# NEOPUUTA.net
KiCad netlist of a schematic drawn in EAGLE
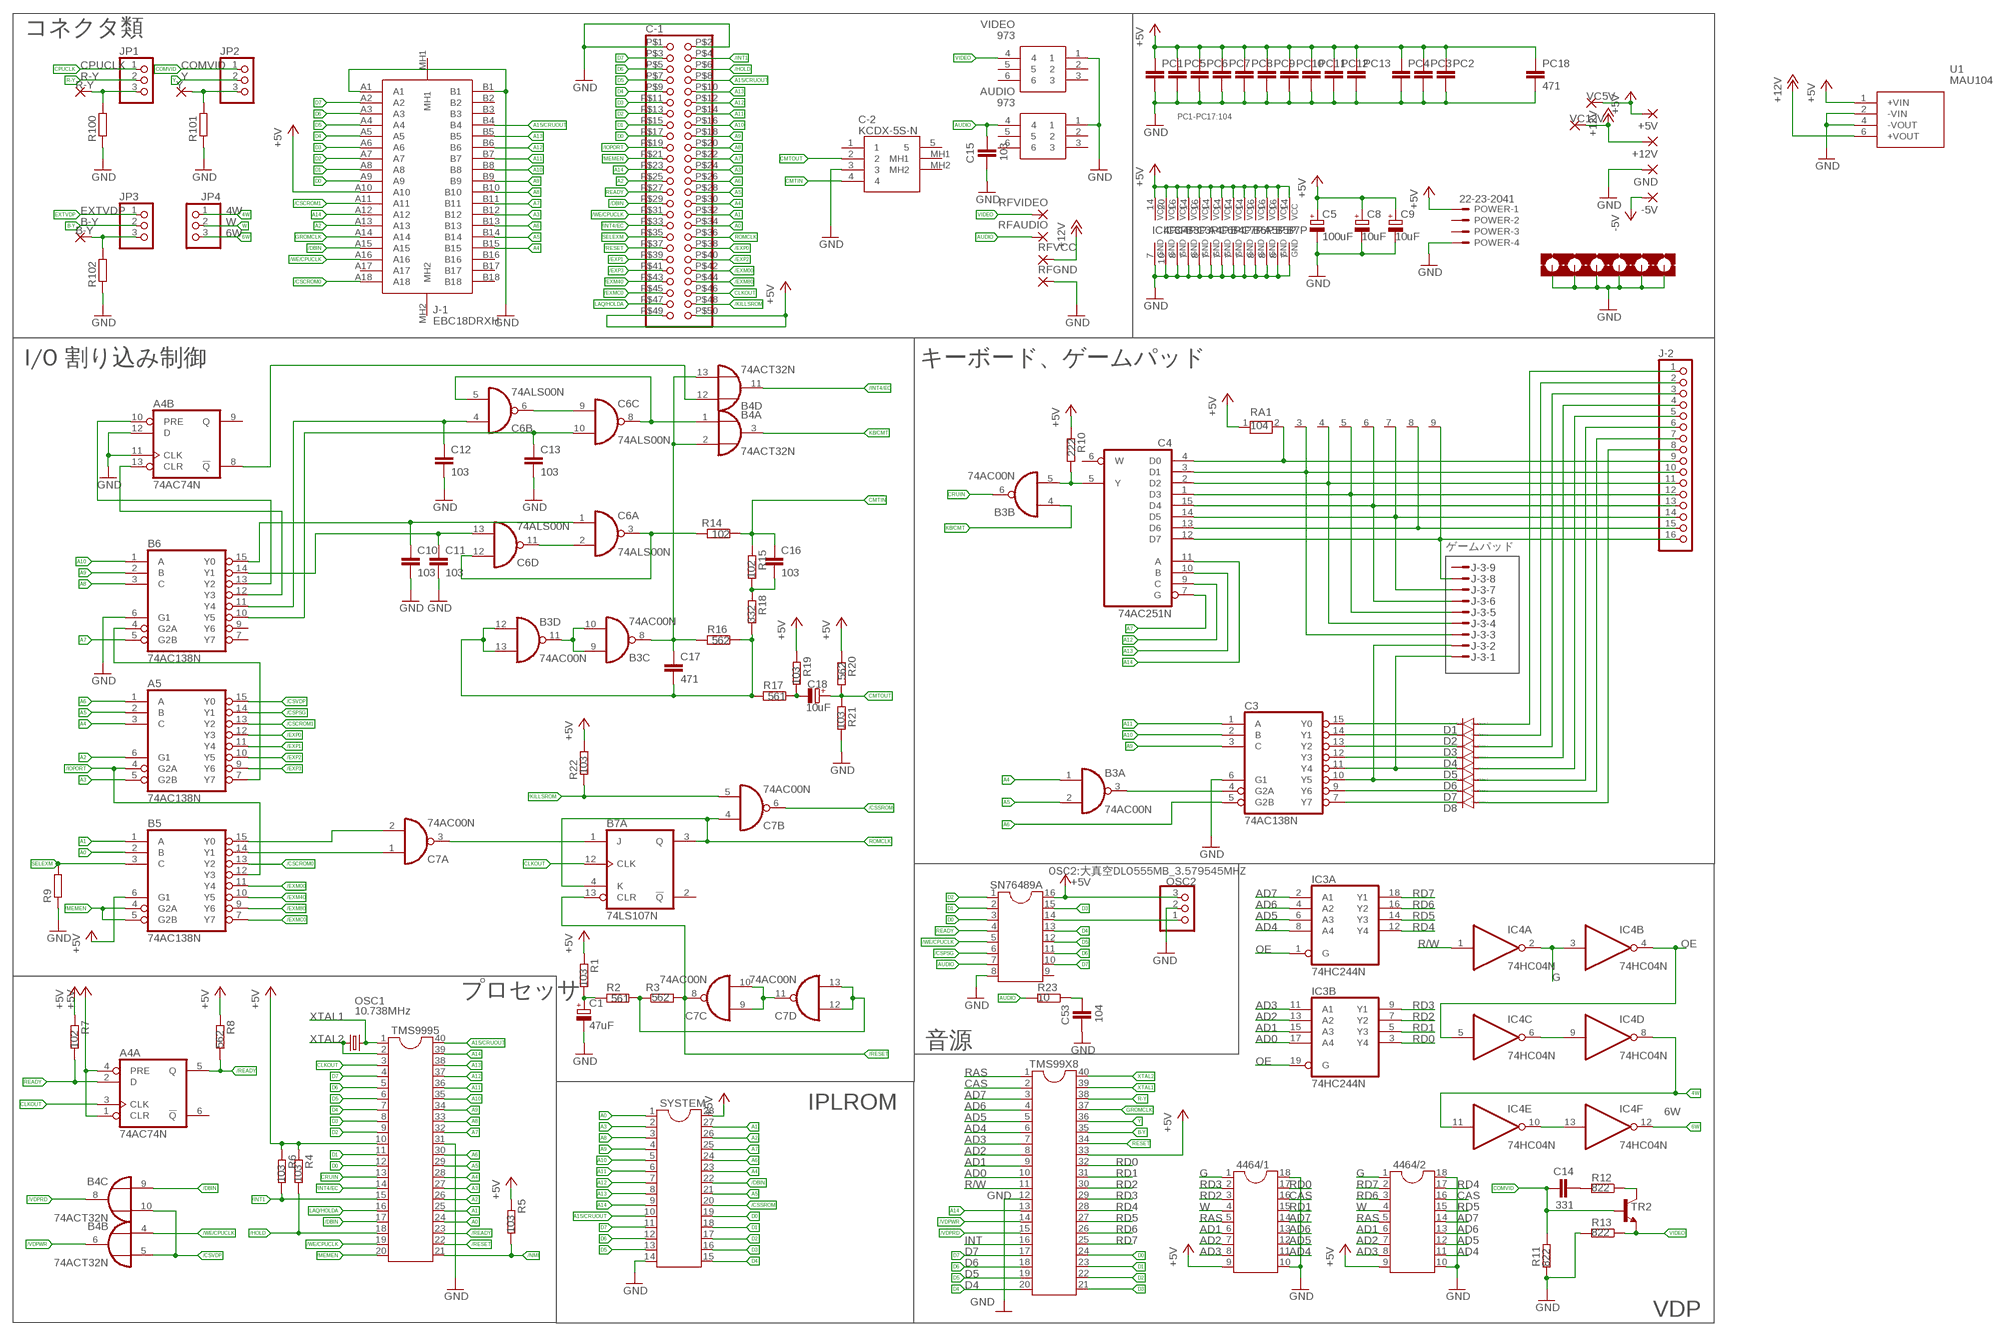
[diagram p0: schematic, sheet 1]

(export (version "E")
  (design (tool "Eeschema 10.0.6"))
  (components
    (comp (ref "+5V")
      (value "3,81/1,4")
      (footprint "eagle-import:3,81_1,4")
      (libsource (lib "eagle-import") (part "3,81/1,4"))
    )
    (comp (ref "+12V")
      (value "3,81/1,4")
      (footprint "eagle-import:3,81_1,4")
      (libsource (lib "eagle-import") (part "3,81/1,4"))
    )
    (comp (ref "-5V")
      (value "3,81/1,4")
      (footprint "eagle-import:3,81_1,4")
      (libsource (lib "eagle-import") (part "3,81/1,4"))
    )
    (comp (ref "4464/1")
      (value "DIL18")
      (footprint "eagle-import:DIL18")
      (libsource (lib "eagle-import") (part "DIL18"))
    )
    (comp (ref "4464/2")
      (value "DIL18")
      (footprint "eagle-import:DIL18")
      (libsource (lib "eagle-import") (part "DIL18"))
    )
    (comp (ref "A4")
      (value "74AC74N")
      (footprint "eagle-import:DIL14")
      (libsource (lib "eagle-import") (part "7474NAC"))
    )
    (comp (ref "A5")
      (value "74AC138N")
      (footprint "eagle-import:DIL16")
      (libsource (lib "eagle-import") (part "74138NAC"))
    )
    (comp (ref "AUDIO")
      (value "973")
      (footprint "eagle-import:973_1")
      (fields (field (name "MOUSER_PART_NUMBER") "534-973"))
      (libsource (lib "eagle-import") (part "973"))
    )
    (comp (ref "B-Y")
      (value "1,6/0,9")
      (footprint "eagle-import:1,6_0,9")
      (libsource (lib "eagle-import") (part "1,6/0,9"))
    )
    (comp (ref "B3")
      (value "74AC00N")
      (footprint "eagle-import:DIL14")
      (libsource (lib "eagle-import") (part "7400NAC"))
    )
    (comp (ref "B4")
      (value "74ACT32N")
      (footprint "eagle-import:DIL14")
      (libsource (lib "eagle-import") (part "7432NACT"))
    )
    (comp (ref "B5")
      (value "74AC138N")
      (footprint "eagle-import:DIL16")
      (libsource (lib "eagle-import") (part "74138NAC"))
    )
    (comp (ref "B6")
      (value "74AC138N")
      (footprint "eagle-import:DIL16")
      (libsource (lib "eagle-import") (part "74138NAC"))
    )
    (comp (ref "B7")
      (value "74LS107N")
      (footprint "eagle-import:DIL14")
      (libsource (lib "eagle-import") (part "74107NLS"))
    )
    (comp (ref "C-1")
      (value "50PI_CARDEDGE_2.54MM_MOTHER")
      (footprint "eagle-import:50PIN_CARDEDGE_2.54MM")
      (libsource (lib "eagle-import") (part "50PI_CARDEDGE_2.54MM_MOTHER"))
    )
    (comp (ref "C-2")
      (value "KCDX-5S-N")
      (footprint "eagle-import:KCDX5SN")
      (fields (field (name "MOUSER_PART_NUMBER") "806-KCDX-5S-N"))
      (libsource (lib "eagle-import") (part "KCDX-5S-N"))
    )
    (comp (ref "C1")
      (value "47uF")
      (footprint "eagle-import:E1,8-4")
      (libsource (lib "eagle-import") (part "CPOL-EUE1.8-4"))
    )
    (comp (ref "C3")
      (value "74AC138N")
      (footprint "eagle-import:DIL16")
      (libsource (lib "eagle-import") (part "74138NAC"))
    )
    (comp (ref "C4")
      (value "74AC251N")
      (footprint "eagle-import:DIL16")
      (libsource (lib "eagle-import") (part "74251NAC"))
    )
    (comp (ref "C5")
      (value "100uF")
      (footprint "eagle-import:E2,5-7")
      (libsource (lib "eagle-import") (part "CPOL-EUE2.5-7"))
    )
    (comp (ref "C6")
      (value "74ALS00N")
      (footprint "eagle-import:DIL14")
      (libsource (lib "eagle-import") (part "7400NALS"))
    )
    (comp (ref "C7")
      (value "74AC00N")
      (footprint "eagle-import:DIL14")
      (libsource (lib "eagle-import") (part "7400NAC"))
    )
    (comp (ref "C8")
      (value "10uF")
      (footprint "eagle-import:E1,8-4")
      (libsource (lib "eagle-import") (part "CPOL-EUE1.8-4"))
    )
    (comp (ref "C9")
      (value "10uF")
      (footprint "eagle-import:E1,8-4")
      (libsource (lib "eagle-import") (part "CPOL-EUE1.8-4"))
    )
    (comp (ref "C10")
      (value "103")
      (footprint "eagle-import:C050-025X075")
      (libsource (lib "eagle-import") (part "C-EU050-025X075"))
    )
    (comp (ref "C11")
      (value "103")
      (footprint "eagle-import:C050-025X075")
      (libsource (lib "eagle-import") (part "C-EU050-025X075"))
    )
    (comp (ref "C12")
      (value "103")
      (footprint "eagle-import:C050-025X075")
      (libsource (lib "eagle-import") (part "C-EU050-025X075"))
    )
    (comp (ref "C13")
      (value "103")
      (footprint "eagle-import:C050-025X075")
      (libsource (lib "eagle-import") (part "C-EU050-025X075"))
    )
    (comp (ref "C14")
      (value "331")
      (footprint "eagle-import:C050-025X075")
      (libsource (lib "eagle-import") (part "C-EU050-025X075"))
    )
    (comp (ref "C15")
      (value "103")
      (footprint "eagle-import:C050-025X075")
      (libsource (lib "eagle-import") (part "C-EU050-025X075"))
    )
    (comp (ref "C16")
      (value "103")
      (footprint "eagle-import:C050-025X075")
      (libsource (lib "eagle-import") (part "C-EU050-025X075"))
    )
    (comp (ref "C17")
      (value "471")
      (footprint "eagle-import:C050-025X075")
      (libsource (lib "eagle-import") (part "C-EU050-025X075"))
    )
    (comp (ref "C18")
      (value "10uF")
      (footprint "eagle-import:E1,8-4")
      (libsource (lib "eagle-import") (part "CPOL-EUE1.8-4"))
    )
    (comp (ref "C53")
      (value "104")
      (footprint "eagle-import:C050-025X075")
      (libsource (lib "eagle-import") (part "C-EU050-025X075"))
    )
    (comp (ref "D1")
      (value "1N4148DO35-10")
      (footprint "eagle-import:DO35-10")
      (libsource (lib "eagle-import") (part "1N4148DO35-10"))
    )
    (comp (ref "D2")
      (value "1N4148DO35-10")
      (footprint "eagle-import:DO35-10")
      (libsource (lib "eagle-import") (part "1N4148DO35-10"))
    )
    (comp (ref "D3")
      (value "1N4148DO35-10")
      (footprint "eagle-import:DO35-10")
      (libsource (lib "eagle-import") (part "1N4148DO35-10"))
    )
    (comp (ref "D4")
      (value "1N4148DO35-10")
      (footprint "eagle-import:DO35-10")
      (libsource (lib "eagle-import") (part "1N4148DO35-10"))
    )
    (comp (ref "D5")
      (value "1N4148DO35-10")
      (footprint "eagle-import:DO35-10")
      (libsource (lib "eagle-import") (part "1N4148DO35-10"))
    )
    (comp (ref "D6")
      (value "1N4148DO35-10")
      (footprint "eagle-import:DO35-10")
      (libsource (lib "eagle-import") (part "1N4148DO35-10"))
    )
    (comp (ref "D7")
      (value "1N4148DO35-10")
      (footprint "eagle-import:DO35-10")
      (libsource (lib "eagle-import") (part "1N4148DO35-10"))
    )
    (comp (ref "D8")
      (value "1N4148DO35-10")
      (footprint "eagle-import:DO35-10")
      (libsource (lib "eagle-import") (part "1N4148DO35-10"))
    )
    (comp (ref "GND")
      (value "3,81/1,4")
      (footprint "eagle-import:3,81_1,4")
      (libsource (lib "eagle-import") (part "3,81/1,4"))
    )
    (comp (ref "H1")
      (value "MOUNT-PAD-SQUARE3.2")
      (footprint "eagle-import:3,2-PAD-SQUARE")
      (libsource (lib "eagle-import") (part "MOUNT-PAD-SQUARE3.2"))
    )
    (comp (ref "H2")
      (value "MOUNT-PAD-SQUARE3.2")
      (footprint "eagle-import:3,2-PAD-SQUARE")
      (libsource (lib "eagle-import") (part "MOUNT-PAD-SQUARE3.2"))
    )
    (comp (ref "H3")
      (value "MOUNT-PAD-SQUARE3.2")
      (footprint "eagle-import:3,2-PAD-SQUARE")
      (libsource (lib "eagle-import") (part "MOUNT-PAD-SQUARE3.2"))
    )
    (comp (ref "H4")
      (value "MOUNT-PAD-SQUARE3.2")
      (footprint "eagle-import:3,2-PAD-SQUARE")
      (libsource (lib "eagle-import") (part "MOUNT-PAD-SQUARE3.2"))
    )
    (comp (ref "H5")
      (value "MOUNT-PAD-SQUARE3.2")
      (footprint "eagle-import:3,2-PAD-SQUARE")
      (libsource (lib "eagle-import") (part "MOUNT-PAD-SQUARE3.2"))
    )
    (comp (ref "H6")
      (value "MOUNT-PAD-SQUARE3.2")
      (footprint "eagle-import:3,2-PAD-SQUARE")
      (libsource (lib "eagle-import") (part "MOUNT-PAD-SQUARE3.2"))
    )
    (comp (ref "IC3")
      (value "74HC244N")
      (footprint "eagle-import:DIL20")
      (libsource (lib "eagle-import") (part "74244NHC"))
    )
    (comp (ref "IC4")
      (value "74HC04N")
      (footprint "eagle-import:DIL14")
      (libsource (lib "eagle-import") (part "7404NHC"))
    )
    (comp (ref "J-1")
      (value "EBC18DRXH")
      (footprint "eagle-import:EBC18DRXH")
      (libsource (lib "eagle-import") (part "EBC18DRXH"))
    )
    (comp (ref "J-2")
      (value "PINHD-1X16")
      (footprint "eagle-import:1X16")
      (libsource (lib "eagle-import") (part "PINHD-1X16"))
    )
    (comp (ref "J-3")
      (value "M09HPS")
      (footprint "eagle-import:M09HP")
      (libsource (lib "eagle-import") (part "M09?SHP"))
    )
    (comp (ref "JP1")
      (value "PINHD-1X3")
      (footprint "eagle-import:1X03")
      (libsource (lib "eagle-import") (part "PINHD-1X3"))
    )
    (comp (ref "JP2")
      (value "PINHD-1X3")
      (footprint "eagle-import:1X03")
      (libsource (lib "eagle-import") (part "PINHD-1X3"))
    )
    (comp (ref "JP3")
      (value "PINHD-1X3")
      (footprint "eagle-import:1X03")
      (libsource (lib "eagle-import") (part "PINHD-1X3"))
    )
    (comp (ref "JP4")
      (value "PINHD-1X3")
      (footprint "eagle-import:1X03")
      (libsource (lib "eagle-import") (part "PINHD-1X3"))
    )
    (comp (ref "OSC1")
      (value "10.738MHz")
      (footprint "eagle-import:HC49_S")
      (libsource (lib "eagle-import") (part "CRYSTALHC49S"))
    )
    (comp (ref "OSC2")
      (value "PINHD-1X3")
      (footprint "eagle-import:1X03")
      (libsource (lib "eagle-import") (part "PINHD-1X3"))
    )
    (comp (ref "PC1")
      (value "C-EU050-025X075")
      (footprint "eagle-import:C050-025X075")
      (libsource (lib "eagle-import") (part "C-EU050-025X075"))
    )
    (comp (ref "PC2")
      (value "C-EU050-025X075")
      (footprint "eagle-import:C050-025X075")
      (libsource (lib "eagle-import") (part "C-EU050-025X075"))
    )
    (comp (ref "PC3")
      (value "C-EU050-025X075")
      (footprint "eagle-import:C050-025X075")
      (libsource (lib "eagle-import") (part "C-EU050-025X075"))
    )
    (comp (ref "PC4")
      (value "C-EU050-025X075")
      (footprint "eagle-import:C050-025X075")
      (libsource (lib "eagle-import") (part "C-EU050-025X075"))
    )
    (comp (ref "PC5")
      (value "C-EU050-025X075")
      (footprint "eagle-import:C050-025X075")
      (libsource (lib "eagle-import") (part "C-EU050-025X075"))
    )
    (comp (ref "PC6")
      (value "C-EU050-025X075")
      (footprint "eagle-import:C050-025X075")
      (libsource (lib "eagle-import") (part "C-EU050-025X075"))
    )
    (comp (ref "PC7")
      (value "C-EU050-025X075")
      (footprint "eagle-import:C050-025X075")
      (libsource (lib "eagle-import") (part "C-EU050-025X075"))
    )
    (comp (ref "PC8")
      (value "C-EU050-025X075")
      (footprint "eagle-import:C050-025X075")
      (libsource (lib "eagle-import") (part "C-EU050-025X075"))
    )
    (comp (ref "PC9")
      (value "C-EU050-025X075")
      (footprint "eagle-import:C050-025X075")
      (libsource (lib "eagle-import") (part "C-EU050-025X075"))
    )
    (comp (ref "PC10")
      (value "C-EU050-025X075")
      (footprint "eagle-import:C050-025X075")
      (libsource (lib "eagle-import") (part "C-EU050-025X075"))
    )
    (comp (ref "PC11")
      (value "C-EU050-025X075")
      (footprint "eagle-import:C050-025X075")
      (libsource (lib "eagle-import") (part "C-EU050-025X075"))
    )
    (comp (ref "PC12")
      (value "C-EU050-025X075")
      (footprint "eagle-import:C050-025X075")
      (libsource (lib "eagle-import") (part "C-EU050-025X075"))
    )
    (comp (ref "PC13")
      (value "C-EU050-025X075")
      (footprint "eagle-import:C050-025X075")
      (libsource (lib "eagle-import") (part "C-EU050-025X075"))
    )
    (comp (ref "PC18")
      (value "471")
      (footprint "eagle-import:C050-025X075")
      (libsource (lib "eagle-import") (part "C-EU050-025X075"))
    )
    (comp (ref "POWER")
      (value "22-23-2041")
      (footprint "eagle-import:22-23-2041")
      (fields (field (name "MF") "MOLEX"))
      (libsource (lib "eagle-import") (part "22-23-2041"))
    )
    (comp (ref "R-Y")
      (value "1,6/0,9")
      (footprint "eagle-import:1,6_0,9")
      (libsource (lib "eagle-import") (part "1,6/0,9"))
    )
    (comp (ref "R1")
      (value "103")
      (footprint "eagle-import:0207_10")
      (libsource (lib "eagle-import") (part "R-EU_0207/10"))
    )
    (comp (ref "R2")
      (value "561")
      (footprint "eagle-import:0207_10")
      (libsource (lib "eagle-import") (part "R-EU_0207/10"))
    )
    (comp (ref "R3")
      (value "562")
      (footprint "eagle-import:0207_10")
      (libsource (lib "eagle-import") (part "R-EU_0207/10"))
    )
    (comp (ref "R4")
      (value "103")
      (footprint "eagle-import:0207_10")
      (libsource (lib "eagle-import") (part "R-EU_0207/10"))
    )
    (comp (ref "R5")
      (value "103")
      (footprint "eagle-import:0207_10")
      (libsource (lib "eagle-import") (part "R-EU_0207/10"))
    )
    (comp (ref "R6")
      (value "103")
      (footprint "eagle-import:0207_10")
      (libsource (lib "eagle-import") (part "R-EU_0207/10"))
    )
    (comp (ref "R7")
      (value "102")
      (footprint "eagle-import:0207_10")
      (libsource (lib "eagle-import") (part "R-EU_0207/10"))
    )
    (comp (ref "R8")
      (value "562")
      (footprint "eagle-import:0207_10")
      (libsource (lib "eagle-import") (part "R-EU_0207/10"))
    )
    (comp (ref "R9")
      (value "R-EU_0207/10")
      (footprint "eagle-import:0207_10")
      (libsource (lib "eagle-import") (part "R-EU_0207/10"))
    )
    (comp (ref "R10")
      (value "222")
      (footprint "eagle-import:0207_10")
      (libsource (lib "eagle-import") (part "R-EU_0207/10"))
    )
    (comp (ref "R11")
      (value "822")
      (footprint "eagle-import:0207_10")
      (libsource (lib "eagle-import") (part "R-EU_0207/10"))
    )
    (comp (ref "R12")
      (value "822")
      (footprint "eagle-import:0207_10")
      (libsource (lib "eagle-import") (part "R-EU_0207/10"))
    )
    (comp (ref "R13")
      (value "822")
      (footprint "eagle-import:0207_10")
      (libsource (lib "eagle-import") (part "R-EU_0207/10"))
    )
    (comp (ref "R14")
      (value "102")
      (footprint "eagle-import:0207_10")
      (libsource (lib "eagle-import") (part "R-EU_0207/10"))
    )
    (comp (ref "R15")
      (value "102")
      (footprint "eagle-import:0207_10")
      (libsource (lib "eagle-import") (part "R-EU_0207/10"))
    )
    (comp (ref "R16")
      (value "562")
      (footprint "eagle-import:0207_10")
      (libsource (lib "eagle-import") (part "R-EU_0207/10"))
    )
    (comp (ref "R17")
      (value "561")
      (footprint "eagle-import:0207_10")
      (libsource (lib "eagle-import") (part "R-EU_0207/10"))
    )
    (comp (ref "R18")
      (value "332")
      (footprint "eagle-import:0207_10")
      (libsource (lib "eagle-import") (part "R-EU_0207/10"))
    )
    (comp (ref "R19")
      (value "103")
      (footprint "eagle-import:0207_10")
      (libsource (lib "eagle-import") (part "R-EU_0207/10"))
    )
    (comp (ref "R20")
      (value "562")
      (footprint "eagle-import:0207_10")
      (libsource (lib "eagle-import") (part "R-EU_0207/10"))
    )
    (comp (ref "R21")
      (value "103")
      (footprint "eagle-import:0207_10")
      (libsource (lib "eagle-import") (part "R-EU_0207/10"))
    )
    (comp (ref "R22")
      (value "103")
      (footprint "eagle-import:0207_10")
      (libsource (lib "eagle-import") (part "R-EU_0207/10"))
    )
    (comp (ref "R23")
      (value "10")
      (footprint "eagle-import:0207_10")
      (libsource (lib "eagle-import") (part "R-EU_0207/10"))
    )
    (comp (ref "R100")
      (value "R-EU_0207/10")
      (footprint "eagle-import:0207_10")
      (libsource (lib "eagle-import") (part "R-EU_0207/10"))
    )
    (comp (ref "R101")
      (value "R-EU_0207/10")
      (footprint "eagle-import:0207_10")
      (libsource (lib "eagle-import") (part "R-EU_0207/10"))
    )
    (comp (ref "R102")
      (value "R-EU_0207/10")
      (footprint "eagle-import:0207_10")
      (libsource (lib "eagle-import") (part "R-EU_0207/10"))
    )
    (comp (ref "RA1")
      (value "104")
      (footprint "eagle-import:RN-9")
      (libsource (lib "eagle-import") (part "RN08"))
    )
    (comp (ref "RFAUDIO")
      (value "3,81/1,4")
      (footprint "eagle-import:3,81_1,4")
      (libsource (lib "eagle-import") (part "3,81/1,4"))
    )
    (comp (ref "RFGND")
      (value "3,81/1,4")
      (footprint "eagle-import:3,81_1,4")
      (libsource (lib "eagle-import") (part "3,81/1,4"))
    )
    (comp (ref "RFVCC")
      (value "3,81/1,4")
      (footprint "eagle-import:3,81_1,4")
      (libsource (lib "eagle-import") (part "3,81/1,4"))
    )
    (comp (ref "RFVIDEO")
      (value "3,81/1,4")
      (footprint "eagle-import:3,81_1,4")
      (libsource (lib "eagle-import") (part "3,81/1,4"))
    )
    (comp (ref "SN76489A")
      (value "DIL16")
      (footprint "eagle-import:DIL16")
      (libsource (lib "eagle-import") (part "DIL16"))
    )
    (comp (ref "SYSTEM")
      (value "DIL28")
      (footprint "eagle-import:DIL28-6")
      (libsource (lib "eagle-import") (part "DIL28"))
    )
    (comp (ref "TMS99X8")
      (value "DIL40")
      (footprint "eagle-import:DIL40")
      (libsource (lib "eagle-import") (part "DIL40"))
    )
    (comp (ref "TMS9995")
      (value "DIL40")
      (footprint "eagle-import:DIL40")
      (libsource (lib "eagle-import") (part "DIL40"))
    )
    (comp (ref "TR2")
      (value "-NPN-TO92-ECB")
      (footprint "eagle-import:TO92-ECB")
      (libsource (lib "eagle-import") (part "-NPN-TO92-ECB"))
    )
    (comp (ref "U1")
      (value "MAU104")
      (footprint "eagle-import:MAU104")
      (libsource (lib "eagle-import") (part "MAU104"))
    )
    (comp (ref "VC5V")
      (value "1,6/0,9")
      (footprint "eagle-import:1,6_0,9")
      (libsource (lib "eagle-import") (part "1,6/0,9"))
    )
    (comp (ref "VC12V")
      (value "1,6/0,9")
      (footprint "eagle-import:1,6_0,9")
      (libsource (lib "eagle-import") (part "1,6/0,9"))
    )
    (comp (ref "VIDEO")
      (value "973")
      (footprint "eagle-import:973_1")
      (fields (field (name "MOUSER_PART_NUMBER") "534-973"))
      (libsource (lib "eagle-import") (part "973"))
    )
    (comp (ref "Y")
      (value "1,6/0,9")
      (footprint "eagle-import:1,6_0,9")
      (libsource (lib "eagle-import") (part "1,6/0,9"))
    )
  )
  (nets
    (net (code "1") (name "+5V") (class "Default")
      (node (ref "+5V") (pin "1") (pinfunction "P_1") (pintype "passive"))
      (node (ref "4464/1") (pin "9") (pinfunction "9_9") (pintype "passive"))
      (node (ref "4464/2") (pin "9") (pinfunction "9_9") (pintype "passive"))
      (node (ref "A4") (pin "1") (pinfunction "CLR_1") (pintype "input"))
      (node (ref "A4") (pin "14") (pinfunction "VCC_14") (pintype "power_in"))
      (node (ref "A4") (pin "4") (pinfunction "PRE_4") (pintype "input"))
      (node (ref "A5") (pin "16") (pinfunction "VCC_16") (pintype "power_in"))
      (node (ref "B3") (pin "14") (pinfunction "VCC_14") (pintype "power_in"))
      (node (ref "B4") (pin "14") (pinfunction "VCC_14") (pintype "power_in"))
      (node (ref "B5") (pin "16") (pinfunction "VCC_16") (pintype "power_in"))
      (node (ref "B5") (pin "6") (pinfunction "G1_6") (pintype "input"))
      (node (ref "B6") (pin "16") (pinfunction "VCC_16") (pintype "power_in"))
      (node (ref "B7") (pin "14") (pinfunction "VCC_14") (pintype "power_in"))
      (node (ref "C-1") (pin "P$49") (pinfunction "49_P$49") (pintype "passive"))
      (node (ref "C-1") (pin "P$50") (pinfunction "50_P$50") (pintype "passive"))
      (node (ref "C3") (pin "16") (pinfunction "VCC_16") (pintype "power_in"))
      (node (ref "C4") (pin "16") (pinfunction "VCC_16") (pintype "power_in"))
      (node (ref "C5") (pin "+") (pinfunction "+_+") (pintype "passive"))
      (node (ref "C6") (pin "14") (pinfunction "VCC_14") (pintype "power_in"))
      (node (ref "C7") (pin "14") (pinfunction "VCC_14") (pintype "power_in"))
      (node (ref "C8") (pin "+") (pinfunction "+_+") (pintype "passive"))
      (node (ref "C9") (pin "+") (pinfunction "+_+") (pintype "passive"))
      (node (ref "IC3") (pin "20") (pinfunction "VCC_20") (pintype "power_in"))
      (node (ref "IC4") (pin "14") (pinfunction "VCC_14") (pintype "power_in"))
      (node (ref "J-1") (pin "A10") (pinfunction "A10_A10") (pintype "bidirectional"))
      (node (ref "OSC2") (pin "3") (pinfunction "3_3") (pintype "passive"))
      (node (ref "PC1") (pin "1") (pinfunction "1_1") (pintype "passive"))
      (node (ref "PC10") (pin "1") (pinfunction "1_1") (pintype "passive"))
      (node (ref "PC11") (pin "1") (pinfunction "1_1") (pintype "passive"))
      (node (ref "PC12") (pin "1") (pinfunction "1_1") (pintype "passive"))
      (node (ref "PC13") (pin "1") (pinfunction "1_1") (pintype "passive"))
      (node (ref "PC18") (pin "1") (pinfunction "1_1") (pintype "passive"))
      (node (ref "PC2") (pin "1") (pinfunction "1_1") (pintype "passive"))
      (node (ref "PC3") (pin "1") (pinfunction "1_1") (pintype "passive"))
      (node (ref "PC4") (pin "1") (pinfunction "1_1") (pintype "passive"))
      (node (ref "PC5") (pin "1") (pinfunction "1_1") (pintype "passive"))
      (node (ref "PC6") (pin "1") (pinfunction "1_1") (pintype "passive"))
      (node (ref "PC7") (pin "1") (pinfunction "1_1") (pintype "passive"))
      (node (ref "PC8") (pin "1") (pinfunction "1_1") (pintype "passive"))
      (node (ref "PC9") (pin "1") (pinfunction "1_1") (pintype "passive"))
      (node (ref "POWER") (pin "1") (pinfunction "S_1") (pintype "passive"))
      (node (ref "R1") (pin "2") (pinfunction "2_2") (pintype "passive"))
      (node (ref "R10") (pin "1") (pinfunction "1_1") (pintype "passive"))
      (node (ref "R19") (pin "2") (pinfunction "2_2") (pintype "passive"))
      (node (ref "R20") (pin "1") (pinfunction "1_1") (pintype "passive"))
      (node (ref "R22") (pin "2") (pinfunction "2_2") (pintype "passive"))
      (node (ref "R4") (pin "2") (pinfunction "2_2") (pintype "passive"))
      (node (ref "R5") (pin "2") (pinfunction "2_2") (pintype "passive"))
      (node (ref "R6") (pin "2") (pinfunction "2_2") (pintype "passive"))
      (node (ref "R7") (pin "2") (pinfunction "2_2") (pintype "passive"))
      (node (ref "R8") (pin "2") (pinfunction "2_2") (pintype "passive"))
      (node (ref "RA1") (pin "1") (pinfunction "1_1") (pintype "passive"))
      (node (ref "SN76489A") (pin "16") (pinfunction "16_16") (pintype "passive"))
      (node (ref "SYSTEM") (pin "28") (pinfunction "28_28") (pintype "passive"))
      (node (ref "TMS9995") (pin "10") (pinfunction "10_10") (pintype "passive"))
      (node (ref "TMS99X8") (pin "33") (pinfunction "33_33") (pintype "passive"))
      (node (ref "U1") (pin "1") (pinfunction "+VIN_1") (pintype "bidirectional"))
      (node (ref "VC5V") (pin "1") (pinfunction "P_1") (pintype "passive"))
    )
    (net (code "2") (name "+12V") (class "Default")
      (node (ref "+12V") (pin "1") (pinfunction "P_1") (pintype "passive"))
      (node (ref "RFVCC") (pin "1") (pinfunction "P_1") (pintype "passive"))
      (node (ref "U1") (pin "6") (pinfunction "+VOUT_6") (pintype "bidirectional"))
      (node (ref "VC12V") (pin "1") (pinfunction "P_1") (pintype "passive"))
    )
    (net (code "3") (name "-5V") (class "Default")
      (node (ref "-5V") (pin "1") (pinfunction "P_1") (pintype "passive"))
    )
    (net (code "4") (name "/AD0") (class "Default")
      (node (ref "IC3") (pin "17") (pinfunction "A4_17") (pintype "input"))
      (node (ref "TMS99X8") (pin "10") (pinfunction "10_10") (pintype "passive"))
    )
    (net (code "5") (name "/AD1") (class "Default")
      (node (ref "4464/1") (pin "6") (pinfunction "6_6") (pintype "passive"))
      (node (ref "4464/2") (pin "6") (pinfunction "6_6") (pintype "passive"))
      (node (ref "IC3") (pin "15") (pinfunction "A3_15") (pintype "input"))
      (node (ref "TMS99X8") (pin "9") (pinfunction "9_9") (pintype "passive"))
    )
    (net (code "6") (name "/AD2") (class "Default")
      (node (ref "4464/1") (pin "7") (pinfunction "7_7") (pintype "passive"))
      (node (ref "4464/2") (pin "7") (pinfunction "7_7") (pintype "passive"))
      (node (ref "IC3") (pin "13") (pinfunction "A2_13") (pintype "input"))
      (node (ref "TMS99X8") (pin "8") (pinfunction "8_8") (pintype "passive"))
    )
    (net (code "7") (name "/AD3") (class "Default")
      (node (ref "4464/1") (pin "8") (pinfunction "8_8") (pintype "passive"))
      (node (ref "4464/2") (pin "8") (pinfunction "8_8") (pintype "passive"))
      (node (ref "IC3") (pin "11") (pinfunction "A1_11") (pintype "input"))
      (node (ref "TMS99X8") (pin "7") (pinfunction "7_7") (pintype "passive"))
    )
    (net (code "8") (name "/AD4") (class "Default")
      (node (ref "4464/1") (pin "11") (pinfunction "11_11") (pintype "passive"))
      (node (ref "4464/2") (pin "11") (pinfunction "11_11") (pintype "passive"))
      (node (ref "IC3") (pin "8") (pinfunction "A4_8") (pintype "input"))
      (node (ref "TMS99X8") (pin "6") (pinfunction "6_6") (pintype "passive"))
    )
    (net (code "9") (name "/AD5") (class "Default")
      (node (ref "4464/1") (pin "12") (pinfunction "12_12") (pintype "passive"))
      (node (ref "4464/2") (pin "12") (pinfunction "12_12") (pintype "passive"))
      (node (ref "IC3") (pin "6") (pinfunction "A3_6") (pintype "input"))
      (node (ref "TMS99X8") (pin "5") (pinfunction "5_5") (pintype "passive"))
    )
    (net (code "10") (name "/AD6") (class "Default")
      (node (ref "4464/1") (pin "13") (pinfunction "13_13") (pintype "passive"))
      (node (ref "4464/2") (pin "13") (pinfunction "13_13") (pintype "passive"))
      (node (ref "IC3") (pin "4") (pinfunction "A2_4") (pintype "input"))
      (node (ref "TMS99X8") (pin "4") (pinfunction "4_4") (pintype "passive"))
    )
    (net (code "11") (name "/AD7") (class "Default")
      (node (ref "4464/1") (pin "14") (pinfunction "14_14") (pintype "passive"))
      (node (ref "4464/2") (pin "14") (pinfunction "14_14") (pintype "passive"))
      (node (ref "IC3") (pin "2") (pinfunction "A1_2") (pintype "input"))
      (node (ref "TMS99X8") (pin "3") (pinfunction "3_3") (pintype "passive"))
    )
    (net (code "12") (name "/CAS") (class "Default")
      (node (ref "4464/1") (pin "16") (pinfunction "16_16") (pintype "passive"))
      (node (ref "4464/2") (pin "16") (pinfunction "16_16") (pintype "passive"))
      (node (ref "TMS99X8") (pin "2") (pinfunction "2_2") (pintype "passive"))
    )
    (net (code "13") (name "/G") (class "Default")
      (node (ref "4464/1") (pin "1") (pinfunction "1_1") (pintype "passive"))
      (node (ref "4464/2") (pin "1") (pinfunction "1_1") (pintype "passive"))
      (node (ref "IC4") (pin "2") (pinfunction "O_2") (pintype "output"))
      (node (ref "IC4") (pin "3") (pinfunction "I_3") (pintype "input"))
    )
    (net (code "14") (name "/INT") (class "Default")
      (node (ref "TMS99X8") (pin "16") (pinfunction "16_16") (pintype "passive"))
    )
    (net (code "15") (name "/OE") (class "Default")
      (node (ref "IC3") (pin "1") (pinfunction "G_1") (pintype "input"))
      (node (ref "IC3") (pin "19") (pinfunction "G_19") (pintype "input"))
      (node (ref "IC4") (pin "4") (pinfunction "O_4") (pintype "output"))
      (node (ref "IC4") (pin "5") (pinfunction "I_5") (pintype "input"))
    )
    (net (code "16") (name "/RAS") (class "Default")
      (node (ref "4464/1") (pin "5") (pinfunction "5_5") (pintype "passive"))
      (node (ref "4464/2") (pin "5") (pinfunction "5_5") (pintype "passive"))
      (node (ref "TMS99X8") (pin "1") (pinfunction "1_1") (pintype "passive"))
    )
    (net (code "17") (name "/RD0") (class "Default")
      (node (ref "4464/1") (pin "17") (pinfunction "17_17") (pintype "passive"))
      (node (ref "IC3") (pin "3") (pinfunction "Y4_3") (pintype "tri_state"))
      (node (ref "TMS99X8") (pin "32") (pinfunction "32_32") (pintype "passive"))
    )
    (net (code "18") (name "/RD1") (class "Default")
      (node (ref "4464/1") (pin "15") (pinfunction "15_15") (pintype "passive"))
      (node (ref "IC3") (pin "5") (pinfunction "Y3_5") (pintype "tri_state"))
      (node (ref "TMS99X8") (pin "31") (pinfunction "31_31") (pintype "passive"))
    )
    (net (code "19") (name "/RD2") (class "Default")
      (node (ref "4464/1") (pin "3") (pinfunction "3_3") (pintype "passive"))
      (node (ref "IC3") (pin "7") (pinfunction "Y2_7") (pintype "tri_state"))
      (node (ref "TMS99X8") (pin "30") (pinfunction "30_30") (pintype "passive"))
    )
    (net (code "20") (name "/RD3") (class "Default")
      (node (ref "4464/1") (pin "2") (pinfunction "2_2") (pintype "passive"))
      (node (ref "IC3") (pin "9") (pinfunction "Y1_9") (pintype "tri_state"))
      (node (ref "TMS99X8") (pin "29") (pinfunction "29_29") (pintype "passive"))
    )
    (net (code "21") (name "/RD4") (class "Default")
      (node (ref "4464/2") (pin "17") (pinfunction "17_17") (pintype "passive"))
      (node (ref "IC3") (pin "12") (pinfunction "Y4_12") (pintype "tri_state"))
      (node (ref "TMS99X8") (pin "28") (pinfunction "28_28") (pintype "passive"))
    )
    (net (code "22") (name "/RD5") (class "Default")
      (node (ref "4464/2") (pin "15") (pinfunction "15_15") (pintype "passive"))
      (node (ref "IC3") (pin "14") (pinfunction "Y3_14") (pintype "tri_state"))
      (node (ref "TMS99X8") (pin "27") (pinfunction "27_27") (pintype "passive"))
    )
    (net (code "23") (name "/RD6") (class "Default")
      (node (ref "4464/2") (pin "3") (pinfunction "3_3") (pintype "passive"))
      (node (ref "IC3") (pin "16") (pinfunction "Y2_16") (pintype "tri_state"))
      (node (ref "TMS99X8") (pin "26") (pinfunction "26_26") (pintype "passive"))
    )
    (net (code "24") (name "/RD7") (class "Default")
      (node (ref "4464/2") (pin "2") (pinfunction "2_2") (pintype "passive"))
      (node (ref "IC3") (pin "18") (pinfunction "Y1_18") (pintype "tri_state"))
      (node (ref "TMS99X8") (pin "25") (pinfunction "25_25") (pintype "passive"))
    )
    (net (code "25") (name "/R{slash}W") (class "Default")
      (node (ref "IC4") (pin "1") (pinfunction "I_1") (pintype "input"))
      (node (ref "TMS99X8") (pin "11") (pinfunction "11_11") (pintype "passive"))
    )
    (net (code "26") (name "4W") (class "Default")
      (node (ref "IC4") (pin "11") (pinfunction "I_11") (pintype "input"))
      (node (ref "IC4") (pin "8") (pinfunction "O_8") (pintype "output"))
      (node (ref "JP4") (pin "1") (pinfunction "1_1") (pintype "passive"))
    )
    (net (code "27") (name "6W") (class "Default")
      (node (ref "IC4") (pin "12") (pinfunction "O_12") (pintype "output"))
      (node (ref "JP4") (pin "3") (pinfunction "3_3") (pintype "passive"))
    )
    (net (code "28") (name "A0") (class "Default")
      (node (ref "B5") (pin "2") (pinfunction "B_2") (pintype "input"))
      (node (ref "C-1") (pin "P$34") (pinfunction "34_P$34") (pintype "passive"))
      (node (ref "SYSTEM") (pin "1") (pinfunction "1_1") (pintype "passive"))
      (node (ref "TMS9995") (pin "24") (pinfunction "24_24") (pintype "passive"))
    )
    (net (code "29") (name "A1") (class "Default")
      (node (ref "B5") (pin "1") (pinfunction "A_1") (pintype "input"))
      (node (ref "C-1") (pin "P$32") (pinfunction "32_P$32") (pintype "passive"))
      (node (ref "SYSTEM") (pin "27") (pinfunction "27_27") (pintype "passive"))
      (node (ref "TMS9995") (pin "25") (pinfunction "25_25") (pintype "passive"))
    )
    (net (code "30") (name "A2") (class "Default")
      (node (ref "A5") (pin "6") (pinfunction "G1_6") (pintype "input"))
      (node (ref "C-1") (pin "P$25") (pinfunction "25_P$25") (pintype "passive"))
      (node (ref "J-1") (pin "A13") (pinfunction "A13_A13") (pintype "bidirectional"))
      (node (ref "SYSTEM") (pin "26") (pinfunction "26_26") (pintype "passive"))
      (node (ref "TMS9995") (pin "26") (pinfunction "26_26") (pintype "passive"))
    )
    (net (code "31") (name "A3") (class "Default")
      (node (ref "A5") (pin "5") (pinfunction "G2B_5") (pintype "input"))
      (node (ref "C-1") (pin "P$24") (pinfunction "24_P$24") (pintype "passive"))
      (node (ref "J-1") (pin "B12") (pinfunction "B12_B12") (pintype "bidirectional"))
      (node (ref "SYSTEM") (pin "2") (pinfunction "2_2") (pintype "passive"))
      (node (ref "TMS9995") (pin "27") (pinfunction "27_27") (pintype "passive"))
    )
    (net (code "32") (name "A4") (class "Default")
      (node (ref "A5") (pin "3") (pinfunction "C_3") (pintype "input"))
      (node (ref "B3") (pin "1") (pinfunction "I0_1") (pintype "input"))
      (node (ref "C-1") (pin "P$30") (pinfunction "30_P$30") (pintype "passive"))
      (node (ref "J-1") (pin "B15") (pinfunction "B15_B15") (pintype "bidirectional"))
      (node (ref "SYSTEM") (pin "23") (pinfunction "23_23") (pintype "passive"))
      (node (ref "TMS9995") (pin "28") (pinfunction "28_28") (pintype "passive"))
    )
    (net (code "33") (name "A5") (class "Default")
      (node (ref "A5") (pin "2") (pinfunction "B_2") (pintype "input"))
      (node (ref "B3") (pin "2") (pinfunction "I1_2") (pintype "input"))
      (node (ref "C-1") (pin "P$28") (pinfunction "28_P$28") (pintype "passive"))
      (node (ref "J-1") (pin "B14") (pinfunction "B14_B14") (pintype "bidirectional"))
      (node (ref "SYSTEM") (pin "21") (pinfunction "21_21") (pintype "passive"))
      (node (ref "TMS9995") (pin "29") (pinfunction "29_29") (pintype "passive"))
    )
    (net (code "34") (name "A6") (class "Default")
      (node (ref "A5") (pin "1") (pinfunction "A_1") (pintype "input"))
      (node (ref "C-1") (pin "P$26") (pinfunction "26_P$26") (pintype "passive"))
      (node (ref "C3") (pin "5") (pinfunction "G2B_5") (pintype "input"))
      (node (ref "J-1") (pin "B13") (pinfunction "B13_B13") (pintype "bidirectional"))
      (node (ref "SYSTEM") (pin "24") (pinfunction "24_24") (pintype "passive"))
      (node (ref "TMS9995") (pin "30") (pinfunction "30_30") (pintype "passive"))
    )
    (net (code "35") (name "A7") (class "Default")
      (node (ref "B6") (pin "5") (pinfunction "G2B_5") (pintype "input"))
      (node (ref "C-1") (pin "P$22") (pinfunction "22_P$22") (pintype "passive"))
      (node (ref "C4") (pin "7") (pinfunction "G_7") (pintype "input"))
      (node (ref "J-1") (pin "B11") (pinfunction "B11_B11") (pintype "bidirectional"))
      (node (ref "SYSTEM") (pin "25") (pinfunction "25_25") (pintype "passive"))
      (node (ref "TMS9995") (pin "32") (pinfunction "32_32") (pintype "passive"))
    )
    (net (code "36") (name "A8") (class "Default")
      (node (ref "B6") (pin "3") (pinfunction "C_3") (pintype "input"))
      (node (ref "C-1") (pin "P$20") (pinfunction "20_P$20") (pintype "passive"))
      (node (ref "J-1") (pin "B10") (pinfunction "B10_B10") (pintype "bidirectional"))
      (node (ref "SYSTEM") (pin "3") (pinfunction "3_3") (pintype "passive"))
      (node (ref "TMS9995") (pin "33") (pinfunction "33_33") (pintype "passive"))
    )
    (net (code "37") (name "A9") (class "Default")
      (node (ref "B6") (pin "2") (pinfunction "B_2") (pintype "input"))
      (node (ref "C-1") (pin "P$18") (pinfunction "18_P$18") (pintype "passive"))
      (node (ref "C3") (pin "3") (pinfunction "C_3") (pintype "input"))
      (node (ref "J-1") (pin "B9") (pinfunction "B9_B9") (pintype "bidirectional"))
      (node (ref "SYSTEM") (pin "4") (pinfunction "4_4") (pintype "passive"))
      (node (ref "TMS9995") (pin "34") (pinfunction "34_34") (pintype "passive"))
    )
    (net (code "38") (name "A10") (class "Default")
      (node (ref "B6") (pin "1") (pinfunction "A_1") (pintype "input"))
      (node (ref "C-1") (pin "P$16") (pinfunction "16_P$16") (pintype "passive"))
      (node (ref "C3") (pin "2") (pinfunction "B_2") (pintype "input"))
      (node (ref "J-1") (pin "B8") (pinfunction "B8_B8") (pintype "bidirectional"))
      (node (ref "SYSTEM") (pin "5") (pinfunction "5_5") (pintype "passive"))
      (node (ref "TMS9995") (pin "35") (pinfunction "35_35") (pintype "passive"))
    )
    (net (code "39") (name "A11") (class "Default")
      (node (ref "C-1") (pin "P$14") (pinfunction "14_P$14") (pintype "passive"))
      (node (ref "C3") (pin "1") (pinfunction "A_1") (pintype "input"))
      (node (ref "J-1") (pin "B7") (pinfunction "B7_B7") (pintype "bidirectional"))
      (node (ref "SYSTEM") (pin "6") (pinfunction "6_6") (pintype "passive"))
      (node (ref "TMS9995") (pin "36") (pinfunction "36_36") (pintype "passive"))
    )
    (net (code "40") (name "A12") (class "Default")
      (node (ref "C-1") (pin "P$12") (pinfunction "12_P$12") (pintype "passive"))
      (node (ref "C4") (pin "9") (pinfunction "C_9") (pintype "input"))
      (node (ref "J-1") (pin "B6") (pinfunction "B6_B6") (pintype "bidirectional"))
      (node (ref "SYSTEM") (pin "7") (pinfunction "7_7") (pintype "passive"))
      (node (ref "TMS9995") (pin "37") (pinfunction "37_37") (pintype "passive"))
    )
    (net (code "41") (name "A13") (class "Default")
      (node (ref "C-1") (pin "P$10") (pinfunction "10_P$10") (pintype "passive"))
      (node (ref "C4") (pin "10") (pinfunction "B_10") (pintype "input"))
      (node (ref "J-1") (pin "B5") (pinfunction "B5_B5") (pintype "bidirectional"))
      (node (ref "SYSTEM") (pin "8") (pinfunction "8_8") (pintype "passive"))
      (node (ref "TMS9995") (pin "38") (pinfunction "38_38") (pintype "passive"))
    )
    (net (code "42") (name "A14") (class "Default")
      (node (ref "C-1") (pin "P$23") (pinfunction "23_P$23") (pintype "passive"))
      (node (ref "C4") (pin "11") (pinfunction "A_11") (pintype "input"))
      (node (ref "J-1") (pin "A12") (pinfunction "A12_A12") (pintype "bidirectional"))
      (node (ref "SYSTEM") (pin "9") (pinfunction "9_9") (pintype "passive"))
      (node (ref "TMS9995") (pin "39") (pinfunction "39_39") (pintype "passive"))
      (node (ref "TMS99X8") (pin "13") (pinfunction "13_13") (pintype "passive"))
    )
    (net (code "43") (name "A15{slash}CRUOUT") (class "Default")
      (node (ref "C-1") (pin "P$8") (pinfunction "8_P$8") (pintype "passive"))
      (node (ref "J-1") (pin "B4") (pinfunction "B4_B4") (pintype "bidirectional"))
      (node (ref "SYSTEM") (pin "10") (pinfunction "10_10") (pintype "passive"))
      (node (ref "TMS9995") (pin "40") (pinfunction "40_40") (pintype "passive"))
    )
    (net (code "44") (name "AUDIO") (class "Default")
      (node (ref "AUDIO") (pin "4") (pinfunction "4_4") (pintype "bidirectional"))
      (node (ref "C15") (pin "2") (pinfunction "2_2") (pintype "passive"))
      (node (ref "R23") (pin "2") (pinfunction "2_2") (pintype "passive"))
      (node (ref "RFAUDIO") (pin "1") (pinfunction "P_1") (pintype "passive"))
      (node (ref "SN76489A") (pin "7") (pinfunction "7_7") (pintype "passive"))
    )
    (net (code "45") (name "B-Y") (class "Default")
      (node (ref "JP3") (pin "2") (pinfunction "2_2") (pintype "passive"))
      (node (ref "TMS99X8") (pin "35") (pinfunction "35_35") (pintype "passive"))
    )
    (net (code "46") (name "CLKOUT") (class "Default")
      (node (ref "A4") (pin "3") (pinfunction "CLK_3") (pintype "input"))
      (node (ref "B7") (pin "12") (pinfunction "CLK_12") (pintype "input"))
      (node (ref "C-1") (pin "P$46") (pinfunction "46_P$46") (pintype "passive"))
      (node (ref "TMS9995") (pin "3") (pinfunction "3_3") (pintype "passive"))
    )
    (net (code "47") (name "CMTIN") (class "Default")
      (node (ref "C-2") (pin "4") (pinfunction "4_4") (pintype "bidirectional"))
      (node (ref "C16") (pin "1") (pinfunction "1_1") (pintype "passive"))
      (node (ref "R14") (pin "1") (pinfunction "1_1") (pintype "passive"))
      (node (ref "R15") (pin "2") (pinfunction "2_2") (pintype "passive"))
    )
    (net (code "48") (name "CMTOUT") (class "Default")
      (node (ref "C-2") (pin "2") (pinfunction "2_2") (pintype "bidirectional"))
      (node (ref "C18") (pin "+") (pinfunction "+_+") (pintype "passive"))
      (node (ref "R20") (pin "2") (pinfunction "2_2") (pintype "passive"))
      (node (ref "R21") (pin "2") (pinfunction "2_2") (pintype "passive"))
    )
    (net (code "49") (name "COMVID") (class "Default")
      (node (ref "C14") (pin "1") (pinfunction "1_1") (pintype "passive"))
      (node (ref "JP2") (pin "1") (pinfunction "1_1") (pintype "passive"))
      (node (ref "R11") (pin "1") (pinfunction "1_1") (pintype "passive"))
      (node (ref "TR2") (pin "B") (pinfunction "B_B") (pintype "passive"))
    )
    (net (code "50") (name "CPUCLK") (class "Default")
      (node (ref "JP1") (pin "1") (pinfunction "1_1") (pintype "passive"))
    )
    (net (code "51") (name "CRUIN") (class "Default")
      (node (ref "B3") (pin "6") (pinfunction "O_6") (pintype "output"))
      (node (ref "TMS9995") (pin "13") (pinfunction "13_13") (pintype "passive"))
    )
    (net (code "52") (name "D0") (class "Default")
      (node (ref "C-1") (pin "P$17") (pinfunction "17_P$17") (pintype "passive"))
      (node (ref "J-1") (pin "A9") (pinfunction "A9_A9") (pintype "bidirectional"))
      (node (ref "SN76489A") (pin "3") (pinfunction "3_3") (pintype "passive"))
      (node (ref "SYSTEM") (pin "19") (pinfunction "19_19") (pintype "passive"))
      (node (ref "TMS9995") (pin "12") (pinfunction "12_12") (pintype "passive"))
      (node (ref "TMS99X8") (pin "24") (pinfunction "24_24") (pintype "passive"))
    )
    (net (code "53") (name "D1") (class "Default")
      (node (ref "C-1") (pin "P$15") (pinfunction "15_P$15") (pintype "passive"))
      (node (ref "J-1") (pin "A8") (pinfunction "A8_A8") (pintype "bidirectional"))
      (node (ref "SN76489A") (pin "2") (pinfunction "2_2") (pintype "passive"))
      (node (ref "SYSTEM") (pin "18") (pinfunction "18_18") (pintype "passive"))
      (node (ref "TMS9995") (pin "11") (pinfunction "11_11") (pintype "passive"))
      (node (ref "TMS99X8") (pin "23") (pinfunction "23_23") (pintype "passive"))
    )
    (net (code "54") (name "D2") (class "Default")
      (node (ref "C-1") (pin "P$13") (pinfunction "13_P$13") (pintype "passive"))
      (node (ref "J-1") (pin "A7") (pinfunction "A7_A7") (pintype "bidirectional"))
      (node (ref "SN76489A") (pin "1") (pinfunction "1_1") (pintype "passive"))
      (node (ref "SYSTEM") (pin "17") (pinfunction "17_17") (pintype "passive"))
      (node (ref "TMS9995") (pin "9") (pinfunction "9_9") (pintype "passive"))
      (node (ref "TMS99X8") (pin "22") (pinfunction "22_22") (pintype "passive"))
    )
    (net (code "55") (name "D3") (class "Default")
      (node (ref "C-1") (pin "P$11") (pinfunction "11_P$11") (pintype "passive"))
      (node (ref "J-1") (pin "A6") (pinfunction "A6_A6") (pintype "bidirectional"))
      (node (ref "SN76489A") (pin "15") (pinfunction "15_15") (pintype "passive"))
      (node (ref "SYSTEM") (pin "16") (pinfunction "16_16") (pintype "passive"))
      (node (ref "TMS9995") (pin "8") (pinfunction "8_8") (pintype "passive"))
      (node (ref "TMS99X8") (pin "21") (pinfunction "21_21") (pintype "passive"))
    )
    (net (code "56") (name "D4") (class "Default")
      (node (ref "C-1") (pin "P$9") (pinfunction "9_P$9") (pintype "passive"))
      (node (ref "J-1") (pin "A5") (pinfunction "A5_A5") (pintype "bidirectional"))
      (node (ref "SN76489A") (pin "13") (pinfunction "13_13") (pintype "passive"))
      (node (ref "SYSTEM") (pin "15") (pinfunction "15_15") (pintype "passive"))
      (node (ref "TMS9995") (pin "7") (pinfunction "7_7") (pintype "passive"))
      (node (ref "TMS99X8") (pin "20") (pinfunction "20_20") (pintype "passive"))
    )
    (net (code "57") (name "D5") (class "Default")
      (node (ref "C-1") (pin "P$7") (pinfunction "7_P$7") (pintype "passive"))
      (node (ref "J-1") (pin "A4") (pinfunction "A4_A4") (pintype "bidirectional"))
      (node (ref "SN76489A") (pin "12") (pinfunction "12_12") (pintype "passive"))
      (node (ref "SYSTEM") (pin "13") (pinfunction "13_13") (pintype "passive"))
      (node (ref "TMS9995") (pin "6") (pinfunction "6_6") (pintype "passive"))
      (node (ref "TMS99X8") (pin "19") (pinfunction "19_19") (pintype "passive"))
    )
    (net (code "58") (name "D6") (class "Default")
      (node (ref "C-1") (pin "P$5") (pinfunction "5_P$5") (pintype "passive"))
      (node (ref "J-1") (pin "A3") (pinfunction "A3_A3") (pintype "bidirectional"))
      (node (ref "SN76489A") (pin "11") (pinfunction "11_11") (pintype "passive"))
      (node (ref "SYSTEM") (pin "12") (pinfunction "12_12") (pintype "passive"))
      (node (ref "TMS9995") (pin "5") (pinfunction "5_5") (pintype "passive"))
      (node (ref "TMS99X8") (pin "18") (pinfunction "18_18") (pintype "passive"))
    )
    (net (code "59") (name "D7") (class "Default")
      (node (ref "C-1") (pin "P$3") (pinfunction "3_P$3") (pintype "passive"))
      (node (ref "J-1") (pin "A2") (pinfunction "A2_A2") (pintype "bidirectional"))
      (node (ref "SN76489A") (pin "10") (pinfunction "10_10") (pintype "passive"))
      (node (ref "SYSTEM") (pin "11") (pinfunction "11_11") (pintype "passive"))
      (node (ref "TMS9995") (pin "4") (pinfunction "4_4") (pintype "passive"))
      (node (ref "TMS99X8") (pin "17") (pinfunction "17_17") (pintype "passive"))
    )
    (net (code "60") (name "EXTVDP") (class "Default")
      (node (ref "JP3") (pin "1") (pinfunction "1_1") (pintype "passive"))
    )
    (net (code "61") (name "GND") (class "Default")
      (node (ref "4464/1") (pin "10") (pinfunction "10_10") (pintype "passive"))
      (node (ref "4464/1") (pin "18") (pinfunction "18_18") (pintype "passive"))
      (node (ref "4464/2") (pin "10") (pinfunction "10_10") (pintype "passive"))
      (node (ref "4464/2") (pin "18") (pinfunction "18_18") (pintype "passive"))
      (node (ref "A4") (pin "11") (pinfunction "CLK_11") (pintype "input"))
      (node (ref "A4") (pin "12") (pinfunction "D_12") (pintype "input"))
      (node (ref "A4") (pin "7") (pinfunction "GND_7") (pintype "power_in"))
      (node (ref "A5") (pin "8") (pinfunction "GND_8") (pintype "power_in"))
      (node (ref "AUDIO") (pin "1") (pinfunction "1_1") (pintype "bidirectional"))
      (node (ref "B3") (pin "7") (pinfunction "GND_7") (pintype "power_in"))
      (node (ref "B4") (pin "7") (pinfunction "GND_7") (pintype "power_in"))
      (node (ref "B5") (pin "8") (pinfunction "GND_8") (pintype "power_in"))
      (node (ref "B6") (pin "6") (pinfunction "G1_6") (pintype "input"))
      (node (ref "B6") (pin "8") (pinfunction "GND_8") (pintype "power_in"))
      (node (ref "B7") (pin "7") (pinfunction "GND_7") (pintype "power_in"))
      (node (ref "C-1") (pin "P$1") (pinfunction "1_P$1") (pintype "passive"))
      (node (ref "C-1") (pin "P$2") (pinfunction "2_P$2") (pintype "passive"))
      (node (ref "C-2") (pin "3") (pinfunction "3_3") (pintype "bidirectional"))
      (node (ref "C1") (pin "-") (pinfunction "-_-") (pintype "passive"))
      (node (ref "C10") (pin "2") (pinfunction "2_2") (pintype "passive"))
      (node (ref "C11") (pin "2") (pinfunction "2_2") (pintype "passive"))
      (node (ref "C12") (pin "2") (pinfunction "2_2") (pintype "passive"))
      (node (ref "C13") (pin "2") (pinfunction "2_2") (pintype "passive"))
      (node (ref "C15") (pin "1") (pinfunction "1_1") (pintype "passive"))
      (node (ref "C3") (pin "6") (pinfunction "G1_6") (pintype "input"))
      (node (ref "C3") (pin "8") (pinfunction "GND_8") (pintype "power_in"))
      (node (ref "C4") (pin "8") (pinfunction "GND_8") (pintype "power_in"))
      (node (ref "C5") (pin "-") (pinfunction "-_-") (pintype "passive"))
      (node (ref "C53") (pin "1") (pinfunction "1_1") (pintype "passive"))
      (node (ref "C6") (pin "7") (pinfunction "GND_7") (pintype "power_in"))
      (node (ref "C7") (pin "7") (pinfunction "GND_7") (pintype "power_in"))
      (node (ref "C8") (pin "-") (pinfunction "-_-") (pintype "passive"))
      (node (ref "C9") (pin "-") (pinfunction "-_-") (pintype "passive"))
      (node (ref "GND") (pin "1") (pinfunction "P_1") (pintype "passive"))
      (node (ref "H1") (pin "B3,2") (pinfunction "MOUNT_B3,2") (pintype "passive"))
      (node (ref "H2") (pin "B3,2") (pinfunction "MOUNT_B3,2") (pintype "passive"))
      (node (ref "H3") (pin "B3,2") (pinfunction "MOUNT_B3,2") (pintype "passive"))
      (node (ref "H4") (pin "B3,2") (pinfunction "MOUNT_B3,2") (pintype "passive"))
      (node (ref "H5") (pin "B3,2") (pinfunction "MOUNT_B3,2") (pintype "passive"))
      (node (ref "H6") (pin "B3,2") (pinfunction "MOUNT_B3,2") (pintype "passive"))
      (node (ref "IC3") (pin "10") (pinfunction "GND_10") (pintype "power_in"))
      (node (ref "IC4") (pin "7") (pinfunction "GND_7") (pintype "power_in"))
      (node (ref "J-1") (pin "A1") (pinfunction "A1_A1") (pintype "bidirectional"))
      (node (ref "J-1") (pin "B1") (pinfunction "B1_B1") (pintype "bidirectional"))
      (node (ref "OSC2") (pin "2") (pinfunction "2_2") (pintype "passive"))
      (node (ref "PC1") (pin "2") (pinfunction "2_2") (pintype "passive"))
      (node (ref "PC10") (pin "2") (pinfunction "2_2") (pintype "passive"))
      (node (ref "PC11") (pin "2") (pinfunction "2_2") (pintype "passive"))
      (node (ref "PC12") (pin "2") (pinfunction "2_2") (pintype "passive"))
      (node (ref "PC13") (pin "2") (pinfunction "2_2") (pintype "passive"))
      (node (ref "PC18") (pin "2") (pinfunction "2_2") (pintype "passive"))
      (node (ref "PC2") (pin "2") (pinfunction "2_2") (pintype "passive"))
      (node (ref "PC3") (pin "2") (pinfunction "2_2") (pintype "passive"))
      (node (ref "PC4") (pin "2") (pinfunction "2_2") (pintype "passive"))
      (node (ref "PC5") (pin "2") (pinfunction "2_2") (pintype "passive"))
      (node (ref "PC6") (pin "2") (pinfunction "2_2") (pintype "passive"))
      (node (ref "PC7") (pin "2") (pinfunction "2_2") (pintype "passive"))
      (node (ref "PC8") (pin "2") (pinfunction "2_2") (pintype "passive"))
      (node (ref "PC9") (pin "2") (pinfunction "2_2") (pintype "passive"))
      (node (ref "POWER") (pin "4") (pinfunction "S_4") (pintype "passive"))
      (node (ref "R100") (pin "1") (pinfunction "1_1") (pintype "passive"))
      (node (ref "R101") (pin "1") (pinfunction "1_1") (pintype "passive"))
      (node (ref "R102") (pin "1") (pinfunction "1_1") (pintype "passive"))
      (node (ref "R11") (pin "2") (pinfunction "2_2") (pintype "passive"))
      (node (ref "R13") (pin "2") (pinfunction "2_2") (pintype "passive"))
      (node (ref "R21") (pin "1") (pinfunction "1_1") (pintype "passive"))
      (node (ref "R9") (pin "1") (pinfunction "1_1") (pintype "passive"))
      (node (ref "RFGND") (pin "1") (pinfunction "P_1") (pintype "passive"))
      (node (ref "SN76489A") (pin "8") (pinfunction "8_8") (pintype "passive"))
      (node (ref "SYSTEM") (pin "14") (pinfunction "14_14") (pintype "passive"))
      (node (ref "TMS9995") (pin "31") (pinfunction "31_31") (pintype "passive"))
      (node (ref "TMS99X8") (pin "12") (pinfunction "12_12") (pintype "passive"))
      (node (ref "U1") (pin "2") (pinfunction "-VIN_2") (pintype "bidirectional"))
      (node (ref "U1") (pin "4") (pinfunction "-VOUT_4") (pintype "bidirectional"))
      (node (ref "VIDEO") (pin "1") (pinfunction "1_1") (pintype "bidirectional"))
    )
    (net (code "62") (name "GROMCLK") (class "Default")
      (node (ref "J-1") (pin "A14") (pinfunction "A14_A14") (pintype "bidirectional"))
      (node (ref "TMS99X8") (pin "37") (pinfunction "37_37") (pintype "passive"))
    )
    (net (code "63") (name "KB{slash}CMT") (class "Default")
      (node (ref "B3") (pin "4") (pinfunction "I0_4") (pintype "input"))
      (node (ref "B4") (pin "3") (pinfunction "O_3") (pintype "output"))
    )
    (net (code "64") (name "LAQ{slash}HOLDA") (class "Default")
      (node (ref "C-1") (pin "P$47") (pinfunction "47_P$47") (pintype "passive"))
      (node (ref "TMS9995") (pin "16") (pinfunction "16_16") (pintype "passive"))
    )
    (net (code "65") (name "Net-(A4B-CLR)") (class "Default")
      (node (ref "A4") (pin "13") (pinfunction "CLR_13") (pintype "input"))
      (node (ref "B6") (pin "12") (pinfunction "Y3_12") (pintype "output"))
    )
    (net (code "66") (name "Net-(A4B-PRE)") (class "Default")
      (node (ref "A4") (pin "10") (pinfunction "PRE_10") (pintype "input"))
      (node (ref "B6") (pin "13") (pinfunction "Y2_13") (pintype "output"))
    )
    (net (code "67") (name "Net-(A4B-~{Q})") (class "Default")
      (node (ref "A4") (pin "8") (pinfunction "~{Q}_8") (pintype "output"))
      (node (ref "B4") (pin "12") (pinfunction "I0_12") (pintype "input"))
    )
    (net (code "68") (name "Net-(A5A-Y7)") (class "Default")
      (node (ref "A5") (pin "7") (pinfunction "Y7_7") (pintype "output"))
      (node (ref "B6") (pin "4") (pinfunction "G2A_4") (pintype "input"))
    )
    (net (code "69") (name "Net-(B-Y-P)") (class "Default")
      (node (ref "B-Y") (pin "1") (pinfunction "P_1") (pintype "passive"))
      (node (ref "JP3") (pin "3") (pinfunction "3_3") (pintype "passive"))
      (node (ref "R102") (pin "2") (pinfunction "2_2") (pintype "passive"))
    )
    (net (code "70") (name "Net-(B3A-O)") (class "Default")
      (node (ref "B3") (pin "3") (pinfunction "O_3") (pintype "output"))
      (node (ref "C3") (pin "4") (pinfunction "G2A_4") (pintype "input"))
    )
    (net (code "71") (name "Net-(B3B-I1)") (class "Default")
      (node (ref "B3") (pin "5") (pinfunction "I1_5") (pintype "input"))
      (node (ref "C4") (pin "5") (pinfunction "Y_5") (pintype "tri_state"))
      (node (ref "R10") (pin "2") (pinfunction "2_2") (pintype "passive"))
    )
    (net (code "72") (name "Net-(B3C-I0)") (class "Default")
      (node (ref "B3") (pin "10") (pinfunction "I1_10") (pintype "input"))
      (node (ref "B3") (pin "11") (pinfunction "O_11") (pintype "output"))
      (node (ref "B3") (pin "9") (pinfunction "I0_9") (pintype "input"))
    )
    (net (code "73") (name "Net-(B3C-O)") (class "Default")
      (node (ref "B3") (pin "8") (pinfunction "O_8") (pintype "output"))
      (node (ref "B4") (pin "13") (pinfunction "I1_13") (pintype "input"))
      (node (ref "B4") (pin "2") (pinfunction "I1_2") (pintype "input"))
      (node (ref "C17") (pin "1") (pinfunction "1_1") (pintype "passive"))
      (node (ref "R16") (pin "2") (pinfunction "2_2") (pintype "passive"))
    )
    (net (code "74") (name "Net-(B3D-I0)") (class "Default")
      (node (ref "B3") (pin "12") (pinfunction "I0_12") (pintype "input"))
      (node (ref "B3") (pin "13") (pinfunction "I1_13") (pintype "input"))
      (node (ref "C17") (pin "2") (pinfunction "2_2") (pintype "passive"))
      (node (ref "R16") (pin "1") (pinfunction "1_1") (pintype "passive"))
      (node (ref "R17") (pin "2") (pinfunction "2_2") (pintype "passive"))
      (node (ref "R18") (pin "1") (pinfunction "1_1") (pintype "passive"))
    )
    (net (code "75") (name "Net-(B4A-I0)") (class "Default")
      (node (ref "B4") (pin "1") (pinfunction "I0_1") (pintype "input"))
      (node (ref "C6") (pin "5") (pinfunction "I1_5") (pintype "input"))
      (node (ref "C6") (pin "8") (pinfunction "O_8") (pintype "output"))
    )
    (net (code "76") (name "Net-(B5A-Y0)") (class "Default")
      (node (ref "B5") (pin "15") (pinfunction "Y0_15") (pintype "output"))
      (node (ref "C7") (pin "2") (pinfunction "I1_2") (pintype "input"))
    )
    (net (code "77") (name "Net-(B5A-Y1)") (class "Default")
      (node (ref "B5") (pin "14") (pinfunction "Y1_14") (pintype "output"))
      (node (ref "C7") (pin "1") (pinfunction "I0_1") (pintype "input"))
    )
    (net (code "78") (name "Net-(B6A-Y0)") (class "Default")
      (node (ref "B6") (pin "15") (pinfunction "Y0_15") (pintype "output"))
      (node (ref "C10") (pin "1") (pinfunction "1_1") (pintype "passive"))
      (node (ref "C6") (pin "1") (pinfunction "I0_1") (pintype "input"))
    )
    (net (code "79") (name "Net-(B6A-Y1)") (class "Default")
      (node (ref "B6") (pin "14") (pinfunction "Y1_14") (pintype "output"))
      (node (ref "C11") (pin "1") (pinfunction "1_1") (pintype "passive"))
      (node (ref "C6") (pin "13") (pinfunction "I1_13") (pintype "input"))
    )
    (net (code "80") (name "Net-(B6A-Y4)") (class "Default")
      (node (ref "B6") (pin "11") (pinfunction "Y4_11") (pintype "output"))
      (node (ref "C12") (pin "1") (pinfunction "1_1") (pintype "passive"))
      (node (ref "C6") (pin "4") (pinfunction "I0_4") (pintype "input"))
    )
    (net (code "81") (name "Net-(B6A-Y5)") (class "Default")
      (node (ref "B6") (pin "10") (pinfunction "Y5_10") (pintype "output"))
      (node (ref "C13") (pin "1") (pinfunction "1_1") (pintype "passive"))
      (node (ref "C6") (pin "10") (pinfunction "I1_10") (pintype "input"))
    )
    (net (code "82") (name "Net-(B7A-J)") (class "Default")
      (node (ref "B7") (pin "1") (pinfunction "J_1") (pintype "input"))
      (node (ref "C7") (pin "3") (pinfunction "O_3") (pintype "output"))
    )
    (net (code "83") (name "Net-(C1-Pad+)") (class "Default")
      (node (ref "C1") (pin "+") (pinfunction "+_+") (pintype "passive"))
      (node (ref "R1") (pin "1") (pinfunction "1_1") (pintype "passive"))
      (node (ref "R2") (pin "2") (pinfunction "2_2") (pintype "passive"))
    )
    (net (code "84") (name "Net-(C3A-Y0)") (class "Default")
      (node (ref "C3") (pin "15") (pinfunction "Y0_15") (pintype "output"))
      (node (ref "D1") (pin "C") (pinfunction "C_C") (pintype "passive"))
    )
    (net (code "85") (name "Net-(C3A-Y1)") (class "Default")
      (node (ref "C3") (pin "14") (pinfunction "Y1_14") (pintype "output"))
      (node (ref "D2") (pin "C") (pinfunction "C_C") (pintype "passive"))
    )
    (net (code "86") (name "Net-(C3A-Y2)") (class "Default")
      (node (ref "C3") (pin "13") (pinfunction "Y2_13") (pintype "output"))
      (node (ref "D3") (pin "C") (pinfunction "C_C") (pintype "passive"))
    )
    (net (code "87") (name "Net-(C3A-Y3)") (class "Default")
      (node (ref "C3") (pin "12") (pinfunction "Y3_12") (pintype "output"))
      (node (ref "D4") (pin "C") (pinfunction "C_C") (pintype "passive"))
    )
    (net (code "88") (name "Net-(C3A-Y4)") (class "Default")
      (node (ref "C3") (pin "11") (pinfunction "Y4_11") (pintype "output"))
      (node (ref "D5") (pin "C") (pinfunction "C_C") (pintype "passive"))
      (node (ref "J-3") (pin "1") (pinfunction "M_1") (pintype "passive"))
    )
    (net (code "89") (name "Net-(C3A-Y5)") (class "Default")
      (node (ref "C3") (pin "10") (pinfunction "Y5_10") (pintype "output"))
      (node (ref "D6") (pin "C") (pinfunction "C_C") (pintype "passive"))
      (node (ref "J-3") (pin "2") (pinfunction "M_2") (pintype "passive"))
    )
    (net (code "90") (name "Net-(C3A-Y6)") (class "Default")
      (node (ref "C3") (pin "9") (pinfunction "Y6_9") (pintype "output"))
      (node (ref "D7") (pin "C") (pinfunction "C_C") (pintype "passive"))
    )
    (net (code "91") (name "Net-(C3A-Y7)") (class "Default")
      (node (ref "C3") (pin "7") (pinfunction "Y7_7") (pintype "output"))
      (node (ref "D8") (pin "C") (pinfunction "C_C") (pintype "passive"))
    )
    (net (code "92") (name "Net-(C4A-D0)") (class "Default")
      (node (ref "C4") (pin "4") (pinfunction "D0_4") (pintype "input"))
      (node (ref "J-2") (pin "9") (pinfunction "9_9") (pintype "passive"))
      (node (ref "RA1") (pin "2") (pinfunction "2_2") (pintype "passive"))
    )
    (net (code "93") (name "Net-(C4A-D1)") (class "Default")
      (node (ref "C4") (pin "3") (pinfunction "D1_3") (pintype "input"))
      (node (ref "J-2") (pin "10") (pinfunction "10_10") (pintype "passive"))
      (node (ref "J-3") (pin "3") (pinfunction "M_3") (pintype "passive"))
      (node (ref "RA1") (pin "3") (pinfunction "3_3") (pintype "passive"))
    )
    (net (code "94") (name "Net-(C4A-D2)") (class "Default")
      (node (ref "C4") (pin "2") (pinfunction "D2_2") (pintype "input"))
      (node (ref "J-2") (pin "11") (pinfunction "11_11") (pintype "passive"))
      (node (ref "J-3") (pin "4") (pinfunction "M_4") (pintype "passive"))
      (node (ref "RA1") (pin "4") (pinfunction "4_4") (pintype "passive"))
    )
    (net (code "95") (name "Net-(C4A-D3)") (class "Default")
      (node (ref "C4") (pin "1") (pinfunction "D3_1") (pintype "input"))
      (node (ref "J-2") (pin "12") (pinfunction "12_12") (pintype "passive"))
      (node (ref "J-3") (pin "5") (pinfunction "M_5") (pintype "passive"))
      (node (ref "RA1") (pin "5") (pinfunction "5_5") (pintype "passive"))
    )
    (net (code "96") (name "Net-(C4A-D4)") (class "Default")
      (node (ref "C4") (pin "15") (pinfunction "D4_15") (pintype "input"))
      (node (ref "J-2") (pin "13") (pinfunction "13_13") (pintype "passive"))
      (node (ref "J-3") (pin "6") (pinfunction "M_6") (pintype "passive"))
      (node (ref "RA1") (pin "6") (pinfunction "6_6") (pintype "passive"))
    )
    (net (code "97") (name "Net-(C4A-D5)") (class "Default")
      (node (ref "C4") (pin "14") (pinfunction "D5_14") (pintype "input"))
      (node (ref "J-2") (pin "14") (pinfunction "14_14") (pintype "passive"))
      (node (ref "J-3") (pin "7") (pinfunction "M_7") (pintype "passive"))
      (node (ref "RA1") (pin "7") (pinfunction "7_7") (pintype "passive"))
    )
    (net (code "98") (name "Net-(C4A-D6)") (class "Default")
      (node (ref "C4") (pin "13") (pinfunction "D6_13") (pintype "input"))
      (node (ref "J-2") (pin "15") (pinfunction "15_15") (pintype "passive"))
      (node (ref "RA1") (pin "8") (pinfunction "8_8") (pintype "passive"))
    )
    (net (code "99") (name "Net-(C4A-D7)") (class "Default")
      (node (ref "C4") (pin "12") (pinfunction "D7_12") (pintype "input"))
      (node (ref "J-2") (pin "16") (pinfunction "16_16") (pintype "passive"))
      (node (ref "J-3") (pin "8") (pinfunction "M_8") (pintype "passive"))
      (node (ref "RA1") (pin "9") (pinfunction "9_9") (pintype "passive"))
    )
    (net (code "100") (name "Net-(C6A-I1)") (class "Default")
      (node (ref "C6") (pin "11") (pinfunction "O_11") (pintype "output"))
      (node (ref "C6") (pin "2") (pinfunction "I1_2") (pintype "input"))
    )
    (net (code "101") (name "Net-(C6A-O)") (class "Default")
      (node (ref "C6") (pin "12") (pinfunction "I0_12") (pintype "input"))
      (node (ref "C6") (pin "3") (pinfunction "O_3") (pintype "output"))
      (node (ref "R14") (pin "2") (pinfunction "2_2") (pintype "passive"))
    )
    (net (code "102") (name "Net-(C6B-O)") (class "Default")
      (node (ref "C6") (pin "6") (pinfunction "O_6") (pintype "output"))
      (node (ref "C6") (pin "9") (pinfunction "I0_9") (pintype "input"))
    )
    (net (code "103") (name "Net-(C7C-I0)") (class "Default")
      (node (ref "C7") (pin "10") (pinfunction "I1_10") (pintype "input"))
      (node (ref "C7") (pin "11") (pinfunction "O_11") (pintype "output"))
      (node (ref "C7") (pin "9") (pinfunction "I0_9") (pintype "input"))
    )
    (net (code "104") (name "Net-(C7D-I0)") (class "Default")
      (node (ref "C7") (pin "12") (pinfunction "I0_12") (pintype "input"))
      (node (ref "C7") (pin "13") (pinfunction "I1_13") (pintype "input"))
      (node (ref "R2") (pin "1") (pinfunction "1_1") (pintype "passive"))
      (node (ref "R3") (pin "1") (pinfunction "1_1") (pintype "passive"))
    )
    (net (code "105") (name "Net-(C14-Pad2)") (class "Default")
      (node (ref "C14") (pin "2") (pinfunction "2_2") (pintype "passive"))
      (node (ref "R12") (pin "2") (pinfunction "2_2") (pintype "passive"))
    )
    (net (code "106") (name "Net-(C16-Pad2)") (class "Default")
      (node (ref "C16") (pin "2") (pinfunction "2_2") (pintype "passive"))
      (node (ref "R15") (pin "1") (pinfunction "1_1") (pintype "passive"))
      (node (ref "R18") (pin "2") (pinfunction "2_2") (pintype "passive"))
    )
    (net (code "107") (name "Net-(C18-Pad-)") (class "Default")
      (node (ref "C18") (pin "-") (pinfunction "-_-") (pintype "passive"))
      (node (ref "R17") (pin "1") (pinfunction "1_1") (pintype "passive"))
      (node (ref "R19") (pin "1") (pinfunction "1_1") (pintype "passive"))
    )
    (net (code "108") (name "Net-(C53-Pad2)") (class "Default")
      (node (ref "C53") (pin "2") (pinfunction "2_2") (pintype "passive"))
      (node (ref "R23") (pin "1") (pinfunction "1_1") (pintype "passive"))
    )
    (net (code "109") (name "Net-(D1-PadA)") (class "Default")
      (node (ref "D1") (pin "A") (pinfunction "A_A") (pintype "passive"))
      (node (ref "J-2") (pin "1") (pinfunction "1_1") (pintype "passive"))
    )
    (net (code "110") (name "Net-(D2-PadA)") (class "Default")
      (node (ref "D2") (pin "A") (pinfunction "A_A") (pintype "passive"))
      (node (ref "J-2") (pin "2") (pinfunction "2_2") (pintype "passive"))
    )
    (net (code "111") (name "Net-(D3-PadA)") (class "Default")
      (node (ref "D3") (pin "A") (pinfunction "A_A") (pintype "passive"))
      (node (ref "J-2") (pin "3") (pinfunction "3_3") (pintype "passive"))
    )
    (net (code "112") (name "Net-(D4-PadA)") (class "Default")
      (node (ref "D4") (pin "A") (pinfunction "A_A") (pintype "passive"))
      (node (ref "J-2") (pin "4") (pinfunction "4_4") (pintype "passive"))
    )
    (net (code "113") (name "Net-(D5-PadA)") (class "Default")
      (node (ref "D5") (pin "A") (pinfunction "A_A") (pintype "passive"))
      (node (ref "J-2") (pin "5") (pinfunction "5_5") (pintype "passive"))
    )
    (net (code "114") (name "Net-(D6-PadA)") (class "Default")
      (node (ref "D6") (pin "A") (pinfunction "A_A") (pintype "passive"))
      (node (ref "J-2") (pin "6") (pinfunction "6_6") (pintype "passive"))
    )
    (net (code "115") (name "Net-(D7-PadA)") (class "Default")
      (node (ref "D7") (pin "A") (pinfunction "A_A") (pintype "passive"))
      (node (ref "J-2") (pin "7") (pinfunction "7_7") (pintype "passive"))
    )
    (net (code "116") (name "Net-(D8-PadA)") (class "Default")
      (node (ref "D8") (pin "A") (pinfunction "A_A") (pintype "passive"))
      (node (ref "J-2") (pin "8") (pinfunction "8_8") (pintype "passive"))
    )
    (net (code "117") (name "Net-(IC4C-O)") (class "Default")
      (node (ref "IC4") (pin "6") (pinfunction "O_6") (pintype "output"))
      (node (ref "IC4") (pin "9") (pinfunction "I_9") (pintype "input"))
    )
    (net (code "118") (name "Net-(IC4E-O)") (class "Default")
      (node (ref "IC4") (pin "10") (pinfunction "O_10") (pintype "output"))
      (node (ref "IC4") (pin "13") (pinfunction "I_13") (pintype "input"))
    )
    (net (code "119") (name "Net-(OSC2-Pad1)") (class "Default")
      (node (ref "OSC2") (pin "1") (pinfunction "1_1") (pintype "passive"))
      (node (ref "SN76489A") (pin "14") (pinfunction "14_14") (pintype "passive"))
    )
    (net (code "120") (name "Net-(R-Y-P)") (class "Default")
      (node (ref "JP1") (pin "3") (pinfunction "3_3") (pintype "passive"))
      (node (ref "R-Y") (pin "1") (pinfunction "P_1") (pintype "passive"))
      (node (ref "R100") (pin "2") (pinfunction "2_2") (pintype "passive"))
    )
    (net (code "121") (name "Net-(R12-Pad1)") (class "Default")
      (node (ref "R12") (pin "1") (pinfunction "1_1") (pintype "passive"))
      (node (ref "TR2") (pin "C") (pinfunction "C_C") (pintype "passive"))
    )
    (net (code "122") (name "Net-(Y-P)") (class "Default")
      (node (ref "JP2") (pin "3") (pinfunction "3_3") (pintype "passive"))
      (node (ref "R101") (pin "2") (pinfunction "2_2") (pintype "passive"))
      (node (ref "Y") (pin "1") (pinfunction "P_1") (pintype "passive"))
    )
    (net (code "123") (name "R-Y") (class "Default")
      (node (ref "JP1") (pin "2") (pinfunction "2_2") (pintype "passive"))
      (node (ref "TMS99X8") (pin "38") (pinfunction "38_38") (pintype "passive"))
    )
    (net (code "124") (name "READY") (class "Default")
      (node (ref "A4") (pin "2") (pinfunction "D_2") (pintype "input"))
      (node (ref "C-1") (pin "P$27") (pinfunction "27_P$27") (pintype "passive"))
      (node (ref "R7") (pin "1") (pinfunction "1_1") (pintype "passive"))
      (node (ref "SN76489A") (pin "4") (pinfunction "4_4") (pintype "passive"))
    )
    (net (code "125") (name "RESET") (class "Default")
      (node (ref "TMS99X8") (pin "34") (pinfunction "34_34") (pintype "passive"))
    )
    (net (code "126") (name "ROMCLK") (class "Default")
      (node (ref "B7") (pin "3") (pinfunction "Q_3") (pintype "output"))
      (node (ref "B7") (pin "4") (pinfunction "K_4") (pintype "input"))
      (node (ref "C-1") (pin "P$36") (pinfunction "36_P$36") (pintype "passive"))
      (node (ref "C7") (pin "4") (pinfunction "I0_4") (pintype "input"))
    )
    (net (code "127") (name "SELEXM") (class "Default")
      (node (ref "B5") (pin "3") (pinfunction "C_3") (pintype "input"))
      (node (ref "C-1") (pin "P$35") (pinfunction "35_P$35") (pintype "passive"))
      (node (ref "R9") (pin "2") (pinfunction "2_2") (pintype "passive"))
    )
    (net (code "128") (name "VIDEO") (class "Default")
      (node (ref "R13") (pin "1") (pinfunction "1_1") (pintype "passive"))
      (node (ref "RFVIDEO") (pin "1") (pinfunction "P_1") (pintype "passive"))
      (node (ref "TR2") (pin "E") (pinfunction "E_E") (pintype "passive"))
      (node (ref "VIDEO") (pin "4") (pinfunction "4_4") (pintype "bidirectional"))
    )
    (net (code "129") (name "W") (class "Default")
      (node (ref "4464/1") (pin "4") (pinfunction "4_4") (pintype "passive"))
      (node (ref "4464/2") (pin "4") (pinfunction "4_4") (pintype "passive"))
      (node (ref "JP4") (pin "2") (pinfunction "2_2") (pintype "passive"))
    )
    (net (code "130") (name "XTAL1") (class "Default")
      (node (ref "OSC1") (pin "2") (pinfunction "2_2") (pintype "passive"))
      (node (ref "TMS9995") (pin "1") (pinfunction "1_1") (pintype "passive"))
      (node (ref "TMS99X8") (pin "39") (pinfunction "39_39") (pintype "passive"))
    )
    (net (code "131") (name "XTAL2") (class "Default")
      (node (ref "OSC1") (pin "1") (pinfunction "1_1") (pintype "passive"))
      (node (ref "TMS9995") (pin "2") (pinfunction "2_2") (pintype "passive"))
      (node (ref "TMS99X8") (pin "40") (pinfunction "40_40") (pintype "passive"))
    )
    (net (code "132") (name "Y") (class "Default")
      (node (ref "JP2") (pin "2") (pinfunction "2_2") (pintype "passive"))
      (node (ref "TMS99X8") (pin "36") (pinfunction "36_36") (pintype "passive"))
    )
    (net (code "133") (name "unconnected-(A4A-~{Q}-Pad6)") (class "Default")
      (node (ref "A4") (pin "6") (pinfunction "~{Q}_6") (pintype "output"))
    )
    (net (code "134") (name "unconnected-(A4B-Q-Pad9)") (class "Default")
      (node (ref "A4") (pin "9") (pinfunction "Q_9") (pintype "output"))
    )
    (net (code "135") (name "unconnected-(AUDIO-Pad2)") (class "Default")
      (node (ref "AUDIO") (pin "2") (pinfunction "2_2") (pintype "bidirectional"))
    )
    (net (code "136") (name "unconnected-(AUDIO-Pad3)") (class "Default")
      (node (ref "AUDIO") (pin "3") (pinfunction "3_3") (pintype "bidirectional"))
    )
    (net (code "137") (name "unconnected-(AUDIO-Pad5)") (class "Default")
      (node (ref "AUDIO") (pin "5") (pinfunction "5_5") (pintype "bidirectional"))
    )
    (net (code "138") (name "unconnected-(AUDIO-Pad6)") (class "Default")
      (node (ref "AUDIO") (pin "6") (pinfunction "6_6") (pintype "bidirectional"))
    )
    (net (code "139") (name "unconnected-(B6A-Y6-Pad9)") (class "Default")
      (node (ref "B6") (pin "9") (pinfunction "Y6_9") (pintype "output"))
    )
    (net (code "140") (name "unconnected-(B6A-Y7-Pad7)") (class "Default")
      (node (ref "B6") (pin "7") (pinfunction "Y7_7") (pintype "output"))
    )
    (net (code "141") (name "unconnected-(B7A-~{Q}-Pad2)") (class "Default")
      (node (ref "B7") (pin "2") (pinfunction "~{Q}_2") (pintype "output"))
    )
    (net (code "142") (name "unconnected-(C-2-Pad1)") (class "Default")
      (node (ref "C-2") (pin "1") (pinfunction "1_1") (pintype "bidirectional"))
    )
    (net (code "143") (name "unconnected-(C-2-Pad5)") (class "Default")
      (node (ref "C-2") (pin "5") (pinfunction "5_5") (pintype "bidirectional"))
    )
    (net (code "144") (name "unconnected-(C-2-PadMH1)") (class "Default")
      (node (ref "C-2") (pin "MH1") (pinfunction "MH1_MH1") (pintype "bidirectional"))
    )
    (net (code "145") (name "unconnected-(C-2-PadMH2)") (class "Default")
      (node (ref "C-2") (pin "MH2") (pinfunction "MH2_MH2") (pintype "bidirectional"))
    )
    (net (code "146") (name "unconnected-(C4A-W-Pad6)") (class "Default")
      (node (ref "C4") (pin "6") (pinfunction "W_6") (pintype "tri_state"))
    )
    (net (code "147") (name "unconnected-(J-1-PadA17)") (class "Default")
      (node (ref "J-1") (pin "A17") (pinfunction "A17_A17") (pintype "bidirectional"))
    )
    (net (code "148") (name "unconnected-(J-1-PadB2)") (class "Default")
      (node (ref "J-1") (pin "B2") (pinfunction "B2_B2") (pintype "bidirectional"))
    )
    (net (code "149") (name "unconnected-(J-1-PadB3)") (class "Default")
      (node (ref "J-1") (pin "B3") (pinfunction "B3_B3") (pintype "bidirectional"))
    )
    (net (code "150") (name "unconnected-(J-1-PadB16)") (class "Default")
      (node (ref "J-1") (pin "B16") (pinfunction "B16_B16") (pintype "bidirectional"))
    )
    (net (code "151") (name "unconnected-(J-1-PadB17)") (class "Default")
      (node (ref "J-1") (pin "B17") (pinfunction "B17_B17") (pintype "bidirectional"))
    )
    (net (code "152") (name "unconnected-(J-1-PadB18)") (class "Default")
      (node (ref "J-1") (pin "B18") (pinfunction "B18_B18") (pintype "bidirectional"))
    )
    (net (code "153") (name "unconnected-(J-1-PadMH1)") (class "Default")
      (node (ref "J-1") (pin "MH1") (pinfunction "MH1_MH1") (pintype "bidirectional"))
    )
    (net (code "154") (name "unconnected-(J-1-PadMH2)") (class "Default")
      (node (ref "J-1") (pin "MH2") (pinfunction "MH2_MH2") (pintype "bidirectional"))
    )
    (net (code "155") (name "unconnected-(J-3I-M-Pad9)") (class "Default")
      (node (ref "J-3") (pin "9") (pinfunction "M_9") (pintype "passive"))
    )
    (net (code "156") (name "unconnected-(POWERB-S-Pad2)") (class "Default")
      (node (ref "POWER") (pin "2") (pinfunction "S_2") (pintype "passive"))
    )
    (net (code "157") (name "unconnected-(POWERC-S-Pad3)") (class "Default")
      (node (ref "POWER") (pin "3") (pinfunction "S_3") (pintype "passive"))
    )
    (net (code "158") (name "unconnected-(SN76489A-Pad9)") (class "Default")
      (node (ref "SN76489A") (pin "9") (pinfunction "9_9") (pintype "passive"))
    )
    (net (code "159") (name "unconnected-(VIDEO-Pad2)") (class "Default")
      (node (ref "VIDEO") (pin "2") (pinfunction "2_2") (pintype "bidirectional"))
    )
    (net (code "160") (name "unconnected-(VIDEO-Pad3)") (class "Default")
      (node (ref "VIDEO") (pin "3") (pinfunction "3_3") (pintype "bidirectional"))
    )
    (net (code "161") (name "unconnected-(VIDEO-Pad5)") (class "Default")
      (node (ref "VIDEO") (pin "5") (pinfunction "5_5") (pintype "bidirectional"))
    )
    (net (code "162") (name "unconnected-(VIDEO-Pad6)") (class "Default")
      (node (ref "VIDEO") (pin "6") (pinfunction "6_6") (pintype "bidirectional"))
    )
    (net (code "163") (name "{slash}CSCROM0") (class "Default")
      (node (ref "B5") (pin "13") (pinfunction "Y2_13") (pintype "output"))
      (node (ref "J-1") (pin "A18") (pinfunction "A18_A18") (pintype "bidirectional"))
    )
    (net (code "164") (name "{slash}CSCROM1") (class "Default")
      (node (ref "A5") (pin "13") (pinfunction "Y2_13") (pintype "output"))
      (node (ref "J-1") (pin "A11") (pinfunction "A11_A11") (pintype "bidirectional"))
    )
    (net (code "165") (name "{slash}CSPSG") (class "Default")
      (node (ref "A5") (pin "14") (pinfunction "Y1_14") (pintype "output"))
      (node (ref "SN76489A") (pin "6") (pinfunction "6_6") (pintype "passive"))
    )
    (net (code "166") (name "{slash}CSSROM") (class "Default")
      (node (ref "C7") (pin "6") (pinfunction "O_6") (pintype "output"))
      (node (ref "SYSTEM") (pin "20") (pinfunction "20_20") (pintype "passive"))
    )
    (net (code "167") (name "{slash}CSVDP") (class "Default")
      (node (ref "A5") (pin "15") (pinfunction "Y0_15") (pintype "output"))
      (node (ref "B4") (pin "10") (pinfunction "I1_10") (pintype "input"))
      (node (ref "B4") (pin "5") (pinfunction "I1_5") (pintype "input"))
    )
    (net (code "168") (name "{slash}DBIN") (class "Default")
      (node (ref "B4") (pin "9") (pinfunction "I0_9") (pintype "input"))
      (node (ref "C-1") (pin "P$29") (pinfunction "29_P$29") (pintype "passive"))
      (node (ref "J-1") (pin "A15") (pinfunction "A15_A15") (pintype "bidirectional"))
      (node (ref "SYSTEM") (pin "22") (pinfunction "22_22") (pintype "passive"))
      (node (ref "TMS9995") (pin "17") (pinfunction "17_17") (pintype "passive"))
    )
    (net (code "169") (name "{slash}EXM00") (class "Default")
      (node (ref "B5") (pin "11") (pinfunction "Y4_11") (pintype "output"))
      (node (ref "C-1") (pin "P$42") (pinfunction "42_P$42") (pintype "passive"))
    )
    (net (code "170") (name "{slash}EXM40") (class "Default")
      (node (ref "B5") (pin "10") (pinfunction "Y5_10") (pintype "output"))
      (node (ref "C-1") (pin "P$43") (pinfunction "43_P$43") (pintype "passive"))
    )
    (net (code "171") (name "{slash}EXM80") (class "Default")
      (node (ref "B5") (pin "9") (pinfunction "Y6_9") (pintype "output"))
      (node (ref "C-1") (pin "P$44") (pinfunction "44_P$44") (pintype "passive"))
    )
    (net (code "172") (name "{slash}EXMC0") (class "Default")
      (node (ref "B5") (pin "7") (pinfunction "Y7_7") (pintype "output"))
      (node (ref "C-1") (pin "P$45") (pinfunction "45_P$45") (pintype "passive"))
    )
    (net (code "173") (name "{slash}EXP0") (class "Default")
      (node (ref "A5") (pin "12") (pinfunction "Y3_12") (pintype "output"))
      (node (ref "C-1") (pin "P$38") (pinfunction "38_P$38") (pintype "passive"))
    )
    (net (code "174") (name "{slash}EXP1") (class "Default")
      (node (ref "A5") (pin "11") (pinfunction "Y4_11") (pintype "output"))
      (node (ref "C-1") (pin "P$39") (pinfunction "39_P$39") (pintype "passive"))
    )
    (net (code "175") (name "{slash}EXP2") (class "Default")
      (node (ref "A5") (pin "10") (pinfunction "Y5_10") (pintype "output"))
      (node (ref "C-1") (pin "P$40") (pinfunction "40_P$40") (pintype "passive"))
    )
    (net (code "176") (name "{slash}EXP3") (class "Default")
      (node (ref "A5") (pin "9") (pinfunction "Y6_9") (pintype "output"))
      (node (ref "C-1") (pin "P$41") (pinfunction "41_P$41") (pintype "passive"))
    )
    (net (code "177") (name "{slash}HOLD") (class "Default")
      (node (ref "C-1") (pin "P$6") (pinfunction "6_P$6") (pintype "passive"))
      (node (ref "R4") (pin "1") (pinfunction "1_1") (pintype "passive"))
      (node (ref "TMS9995") (pin "18") (pinfunction "18_18") (pintype "passive"))
    )
    (net (code "178") (name "{slash}INT1") (class "Default")
      (node (ref "C-1") (pin "P$4") (pinfunction "4_P$4") (pintype "passive"))
      (node (ref "R6") (pin "1") (pinfunction "1_1") (pintype "passive"))
      (node (ref "TMS9995") (pin "15") (pinfunction "15_15") (pintype "passive"))
    )
    (net (code "179") (name "{slash}INT4{slash}EC") (class "Default")
      (node (ref "B4") (pin "11") (pinfunction "O_11") (pintype "output"))
      (node (ref "C-1") (pin "P$33") (pinfunction "33_P$33") (pintype "passive"))
      (node (ref "TMS9995") (pin "14") (pinfunction "14_14") (pintype "passive"))
    )
    (net (code "180") (name "{slash}IOPORT") (class "Default")
      (node (ref "A5") (pin "4") (pinfunction "G2A_4") (pintype "input"))
      (node (ref "B5") (pin "12") (pinfunction "Y3_12") (pintype "output"))
      (node (ref "C-1") (pin "P$19") (pinfunction "19_P$19") (pintype "passive"))
    )
    (net (code "181") (name "{slash}KILLSROM") (class "Default")
      (node (ref "C-1") (pin "P$48") (pinfunction "48_P$48") (pintype "passive"))
      (node (ref "C7") (pin "5") (pinfunction "I1_5") (pintype "input"))
      (node (ref "R22") (pin "1") (pinfunction "1_1") (pintype "passive"))
    )
    (net (code "182") (name "{slash}MEMEN") (class "Default")
      (node (ref "B5") (pin "4") (pinfunction "G2A_4") (pintype "input"))
      (node (ref "B5") (pin "5") (pinfunction "G2B_5") (pintype "input"))
      (node (ref "C-1") (pin "P$21") (pinfunction "21_P$21") (pintype "passive"))
      (node (ref "TMS9995") (pin "20") (pinfunction "20_20") (pintype "passive"))
    )
    (net (code "183") (name "{slash}NMI") (class "Default")
      (node (ref "R5") (pin "1") (pinfunction "1_1") (pintype "passive"))
      (node (ref "TMS9995") (pin "21") (pinfunction "21_21") (pintype "passive"))
    )
    (net (code "184") (name "{slash}READY") (class "Default")
      (node (ref "A4") (pin "5") (pinfunction "Q_5") (pintype "output"))
      (node (ref "R8") (pin "1") (pinfunction "1_1") (pintype "passive"))
      (node (ref "TMS9995") (pin "23") (pinfunction "23_23") (pintype "passive"))
    )
    (net (code "185") (name "{slash}RESET") (class "Default")
      (node (ref "B7") (pin "13") (pinfunction "CLR_13") (pintype "input"))
      (node (ref "C-1") (pin "P$37") (pinfunction "37_P$37") (pintype "passive"))
      (node (ref "C7") (pin "8") (pinfunction "O_8") (pintype "output"))
      (node (ref "R3") (pin "2") (pinfunction "2_2") (pintype "passive"))
      (node (ref "TMS9995") (pin "22") (pinfunction "22_22") (pintype "passive"))
    )
    (net (code "186") (name "{slash}VDPRD") (class "Default")
      (node (ref "B4") (pin "8") (pinfunction "O_8") (pintype "output"))
      (node (ref "TMS99X8") (pin "15") (pinfunction "15_15") (pintype "passive"))
    )
    (net (code "187") (name "{slash}VDPWR") (class "Default")
      (node (ref "B4") (pin "6") (pinfunction "O_6") (pintype "output"))
      (node (ref "TMS99X8") (pin "14") (pinfunction "14_14") (pintype "passive"))
    )
    (net (code "188") (name "{slash}WE{slash}CPUCLK") (class "Default")
      (node (ref "B4") (pin "4") (pinfunction "I0_4") (pintype "input"))
      (node (ref "C-1") (pin "P$31") (pinfunction "31_P$31") (pintype "passive"))
      (node (ref "J-1") (pin "A16") (pinfunction "A16_A16") (pintype "bidirectional"))
      (node (ref "SN76489A") (pin "5") (pinfunction "5_5") (pintype "passive"))
      (node (ref "TMS9995") (pin "19") (pinfunction "19_19") (pintype "passive"))
    )
  )
)
